# 11_FPGA_power.net
KiCad netlist of a schematic drawn in Altium Designer
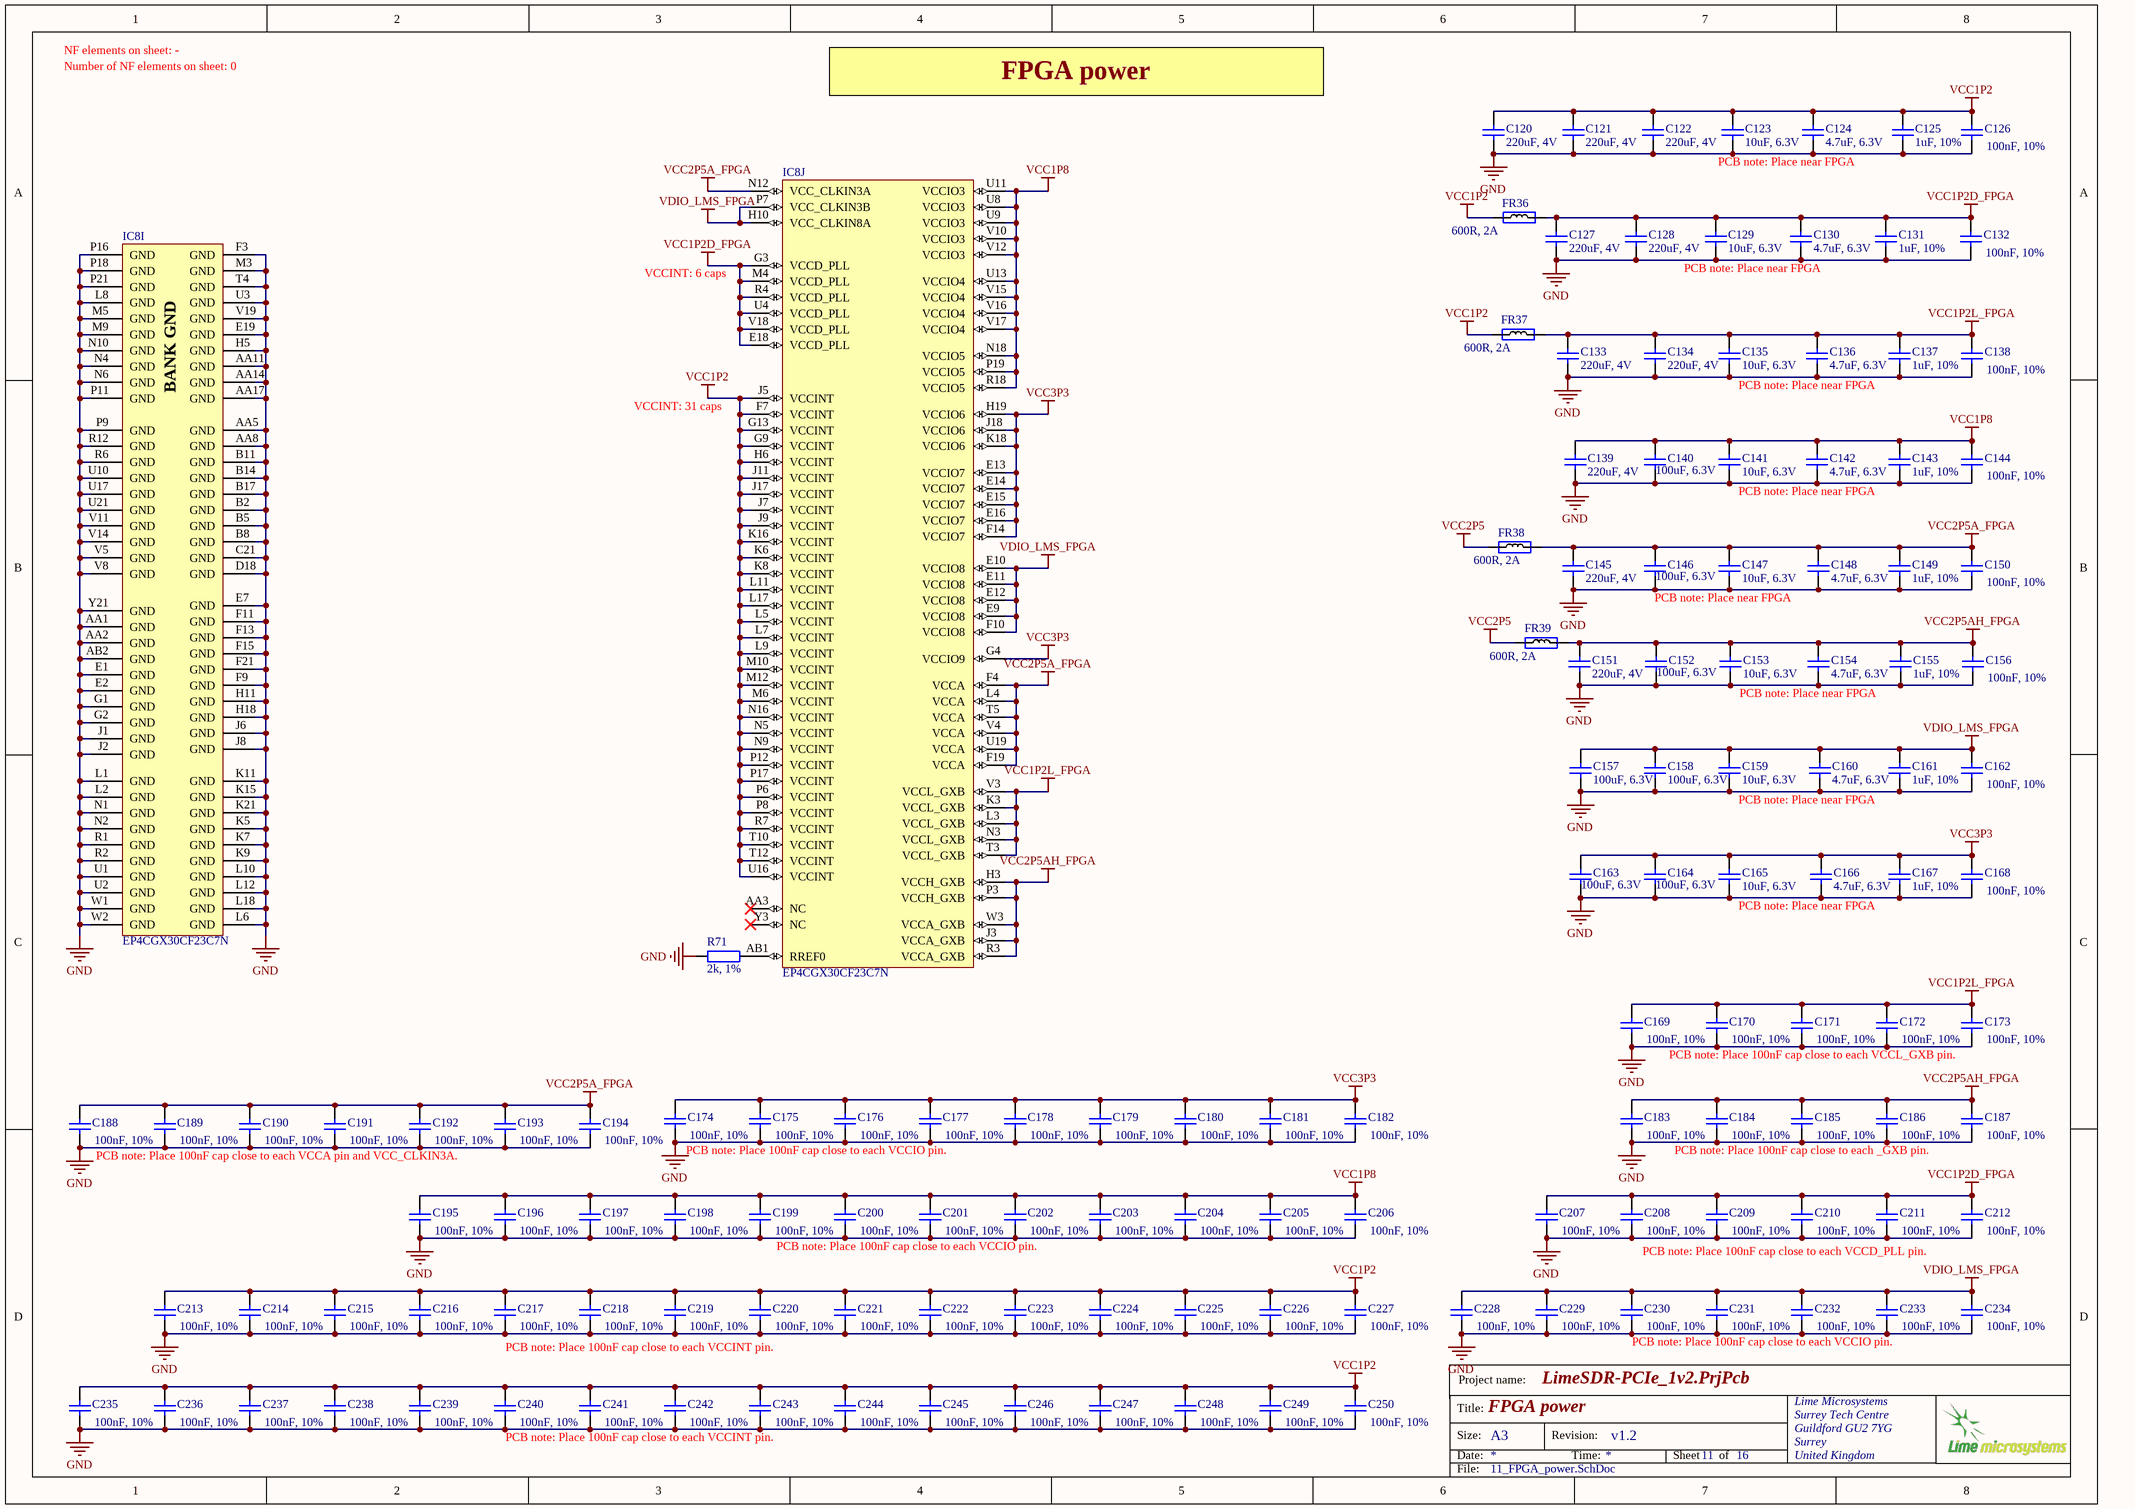
[diagram p0: 11_FPGA_power.SchDoc]

(export (version "E")
  (design (tool "Eeschema 10.0.6"))
  (components
    (comp (ref "C120")
      (value "220uF, 4V")
      (footprint "CAP1206")
      (fields
        (field (name "MANUFACTURER PART NUMBER") "GRM31CR60G227ME11L")
        (field (name "MANUFACTURER") "Murata Electronics North America")
        (field (name "TOLERANCE") "±20%")
      )
      (libsource (lib "LimeFPGAboard_schLib") (part "Cap_1206"))
    )
    (comp (ref "C121")
      (value "220uF, 4V")
      (footprint "CAP1206")
      (fields
        (field (name "MANUFACTURER PART NUMBER") "GRM31CR60G227ME11L")
        (field (name "MANUFACTURER") "Murata Electronics North America")
        (field (name "TOLERANCE") "±20%")
      )
      (libsource (lib "LimeFPGAboard_schLib") (part "Cap_1206"))
    )
    (comp (ref "C122")
      (value "220uF, 4V")
      (footprint "CAP1206")
      (fields
        (field (name "MANUFACTURER PART NUMBER") "GRM31CR60G227ME11L")
        (field (name "MANUFACTURER") "Murata Electronics North America")
        (field (name "TOLERANCE") "±20%")
      )
      (libsource (lib "LimeFPGAboard_schLib") (part "Cap_1206"))
    )
    (comp (ref "C123")
      (value "10uF, 6.3V")
      (footprint "CAP0603")
      (fields (field (name "TOLERANCE") "±20%") (field (name "MANUFACTURER") "Yageo"))
      (libsource (lib "LimeFPGAboard_schLib") (part "Cap_0603"))
    )
    (comp (ref "C124")
      (value "4.7uF, 6.3V")
      (footprint "CAP0402")
      (fields
        (field (name "MANUFACTURER") "Murata Electronics North America")
        (field (name "TOLERANCE") "±20%")
      )
      (libsource (lib "LimeMicroAltiumLib_schLib") (part "Cap_0402"))
    )
    (comp (ref "C125")
      (value "1uF, 10%")
      (footprint "CAP0402")
      (fields (field (name "MANUFACTURER") "TDK"))
      (libsource (lib "LimeMicroAltiumLib_schLib") (part "Cap_0402"))
    )
    (comp (ref "C126")
      (value "100nF, 10%")
      (footprint "CAP0402")
      (fields
        (field (name "TOLERANCE") "10 %")
        (field (name "MANUFACTURER") "Murata Electronics")
        (field (name "MANUFACTURER PART NUMBER") "GRM155R71C104KA88D")
      )
      (libsource (lib "LimeFPGAboard_schLib") (part "Cap_0603"))
    )
    (comp (ref "C127")
      (value "220uF, 4V")
      (footprint "CAP1206")
      (fields
        (field (name "MANUFACTURER PART NUMBER") "GRM31CR60G227ME11L")
        (field (name "MANUFACTURER") "Murata Electronics North America")
        (field (name "TOLERANCE") "±20%")
      )
      (libsource (lib "LimeFPGAboard_schLib") (part "Cap_1206"))
    )
    (comp (ref "C128")
      (value "220uF, 4V")
      (footprint "CAP1206")
      (fields
        (field (name "MANUFACTURER PART NUMBER") "GRM31CR60G227ME11L")
        (field (name "MANUFACTURER") "Murata Electronics North America")
        (field (name "TOLERANCE") "±20%")
      )
      (libsource (lib "LimeFPGAboard_schLib") (part "Cap_1206"))
    )
    (comp (ref "C129")
      (value "10uF, 6.3V")
      (footprint "CAP0603")
      (fields (field (name "TOLERANCE") "±20%") (field (name "MANUFACTURER") "Yageo"))
      (libsource (lib "LimeFPGAboard_schLib") (part "Cap_0603"))
    )
    (comp (ref "C130")
      (value "4.7uF, 6.3V")
      (footprint "CAP0402")
      (fields
        (field (name "MANUFACTURER") "Murata Electronics North America")
        (field (name "TOLERANCE") "±20%")
      )
      (libsource (lib "LimeMicroAltiumLib_schLib") (part "Cap_0402"))
    )
    (comp (ref "C131")
      (value "1uF, 10%")
      (footprint "CAP0402")
      (fields (field (name "MANUFACTURER") "TDK"))
      (libsource (lib "LimeMicroAltiumLib_schLib") (part "Cap_0402"))
    )
    (comp (ref "C132")
      (value "100nF, 10%")
      (footprint "CAP0402")
      (fields
        (field (name "TOLERANCE") "10 %")
        (field (name "MANUFACTURER") "Murata Electronics")
        (field (name "MANUFACTURER PART NUMBER") "GRM155R71C104KA88D")
      )
      (libsource (lib "LimeFPGAboard_schLib") (part "Cap_0603"))
    )
    (comp (ref "C133")
      (value "220uF, 4V")
      (footprint "CAP1206")
      (fields
        (field (name "MANUFACTURER PART NUMBER") "GRM31CR60G227ME11L")
        (field (name "MANUFACTURER") "Murata Electronics North America")
        (field (name "TOLERANCE") "±20%")
      )
      (libsource (lib "LimeFPGAboard_schLib") (part "Cap_1206"))
    )
    (comp (ref "C134")
      (value "220uF, 4V")
      (footprint "CAP1206")
      (fields
        (field (name "MANUFACTURER PART NUMBER") "GRM31CR60G227ME11L")
        (field (name "MANUFACTURER") "Murata Electronics North America")
        (field (name "TOLERANCE") "±20%")
      )
      (libsource (lib "LimeFPGAboard_schLib") (part "Cap_1206"))
    )
    (comp (ref "C135")
      (value "10uF, 6.3V")
      (footprint "CAP0603")
      (fields (field (name "TOLERANCE") "±20%") (field (name "MANUFACTURER") "Yageo"))
      (libsource (lib "LimeFPGAboard_schLib") (part "Cap_0603"))
    )
    (comp (ref "C136")
      (value "4.7uF, 6.3V")
      (footprint "CAP0402")
      (fields
        (field (name "MANUFACTURER") "Murata Electronics North America")
        (field (name "TOLERANCE") "±20%")
      )
      (libsource (lib "LimeMicroAltiumLib_schLib") (part "Cap_0402"))
    )
    (comp (ref "C137")
      (value "1uF, 10%")
      (footprint "CAP0402")
      (fields (field (name "MANUFACTURER") "TDK"))
      (libsource (lib "LimeMicroAltiumLib_schLib") (part "Cap_0402"))
    )
    (comp (ref "C138")
      (value "100nF, 10%")
      (footprint "CAP0402")
      (fields
        (field (name "TOLERANCE") "10 %")
        (field (name "MANUFACTURER") "Murata Electronics")
        (field (name "MANUFACTURER PART NUMBER") "GRM155R71C104KA88D")
      )
      (libsource (lib "LimeFPGAboard_schLib") (part "Cap_0603"))
    )
    (comp (ref "C139")
      (value "220uF, 4V")
      (footprint "CAP1206")
      (fields
        (field (name "MANUFACTURER PART NUMBER") "GRM31CR60G227ME11L")
        (field (name "MANUFACTURER") "Murata Electronics North America")
        (field (name "TOLERANCE") "±20%")
      )
      (libsource (lib "LimeFPGAboard_schLib") (part "Cap_1206"))
    )
    (comp (ref "C140")
      (value "100uF, 6.3V")
      (footprint "CAP1206")
      (fields (field (name "MANUFACTURER") "MURATA"))
      (libsource (lib "LimeFPGAboard_schLib") (part "Cap_1206"))
    )
    (comp (ref "C141")
      (value "10uF, 6.3V")
      (footprint "CAP0603")
      (fields (field (name "TOLERANCE") "±20%") (field (name "MANUFACTURER") "Yageo"))
      (libsource (lib "LimeFPGAboard_schLib") (part "Cap_0603"))
    )
    (comp (ref "C142")
      (value "4.7uF, 6.3V")
      (footprint "CAP0402")
      (fields
        (field (name "MANUFACTURER") "Murata Electronics North America")
        (field (name "TOLERANCE") "±20%")
      )
      (libsource (lib "LimeMicroAltiumLib_schLib") (part "Cap_0402"))
    )
    (comp (ref "C143")
      (value "1uF, 10%")
      (footprint "CAP0402")
      (fields (field (name "MANUFACTURER") "TDK"))
      (libsource (lib "LimeMicroAltiumLib_schLib") (part "Cap_0402"))
    )
    (comp (ref "C144")
      (value "100nF, 10%")
      (footprint "CAP0402")
      (fields
        (field (name "TOLERANCE") "10 %")
        (field (name "MANUFACTURER") "Murata Electronics")
        (field (name "MANUFACTURER PART NUMBER") "GRM155R71C104KA88D")
      )
      (libsource (lib "LimeFPGAboard_schLib") (part "Cap_0603"))
    )
    (comp (ref "C145")
      (value "220uF, 4V")
      (footprint "CAP1206")
      (fields
        (field (name "MANUFACTURER PART NUMBER") "GRM31CR60G227ME11L")
        (field (name "MANUFACTURER") "Murata Electronics North America")
        (field (name "TOLERANCE") "±20%")
      )
      (libsource (lib "LimeFPGAboard_schLib") (part "Cap_1206"))
    )
    (comp (ref "C146")
      (value "100uF, 6.3V")
      (footprint "CAP1206")
      (fields (field (name "MANUFACTURER") "MURATA"))
      (libsource (lib "LimeFPGAboard_schLib") (part "Cap_1206"))
    )
    (comp (ref "C147")
      (value "10uF, 6.3V")
      (footprint "CAP0603")
      (fields (field (name "TOLERANCE") "±20%") (field (name "MANUFACTURER") "Yageo"))
      (libsource (lib "LimeFPGAboard_schLib") (part "Cap_0603"))
    )
    (comp (ref "C148")
      (value "4.7uF, 6.3V")
      (footprint "CAP0402")
      (fields
        (field (name "MANUFACTURER") "Murata Electronics North America")
        (field (name "TOLERANCE") "±20%")
      )
      (libsource (lib "LimeMicroAltiumLib_schLib") (part "Cap_0402"))
    )
    (comp (ref "C149")
      (value "1uF, 10%")
      (footprint "CAP0402")
      (fields (field (name "MANUFACTURER") "TDK"))
      (libsource (lib "LimeMicroAltiumLib_schLib") (part "Cap_0402"))
    )
    (comp (ref "C150")
      (value "100nF, 10%")
      (footprint "CAP0402")
      (fields
        (field (name "TOLERANCE") "10 %")
        (field (name "MANUFACTURER") "Murata Electronics")
        (field (name "MANUFACTURER PART NUMBER") "GRM155R71C104KA88D")
      )
      (libsource (lib "LimeFPGAboard_schLib") (part "Cap_0603"))
    )
    (comp (ref "C151")
      (value "220uF, 4V")
      (footprint "CAP1206")
      (fields
        (field (name "MANUFACTURER PART NUMBER") "GRM31CR60G227ME11L")
        (field (name "MANUFACTURER") "Murata Electronics North America")
        (field (name "TOLERANCE") "±20%")
      )
      (libsource (lib "LimeFPGAboard_schLib") (part "Cap_1206"))
    )
    (comp (ref "C152")
      (value "100uF, 6.3V")
      (footprint "CAP1206")
      (fields (field (name "MANUFACTURER") "MURATA"))
      (libsource (lib "LimeFPGAboard_schLib") (part "Cap_1206"))
    )
    (comp (ref "C153")
      (value "10uF, 6.3V")
      (footprint "CAP0603")
      (fields (field (name "TOLERANCE") "±20%") (field (name "MANUFACTURER") "Yageo"))
      (libsource (lib "LimeFPGAboard_schLib") (part "Cap_0603"))
    )
    (comp (ref "C154")
      (value "4.7uF, 6.3V")
      (footprint "CAP0402")
      (fields
        (field (name "MANUFACTURER") "Murata Electronics North America")
        (field (name "TOLERANCE") "±20%")
      )
      (libsource (lib "LimeMicroAltiumLib_schLib") (part "Cap_0402"))
    )
    (comp (ref "C155")
      (value "1uF, 10%")
      (footprint "CAP0402")
      (fields (field (name "MANUFACTURER") "TDK"))
      (libsource (lib "LimeMicroAltiumLib_schLib") (part "Cap_0402"))
    )
    (comp (ref "C156")
      (value "100nF, 10%")
      (footprint "CAP0402")
      (fields
        (field (name "TOLERANCE") "10 %")
        (field (name "MANUFACTURER") "Murata Electronics")
        (field (name "MANUFACTURER PART NUMBER") "GRM155R71C104KA88D")
      )
      (libsource (lib "LimeFPGAboard_schLib") (part "Cap_0603"))
    )
    (comp (ref "C157")
      (value "100uF, 6.3V")
      (footprint "CAP1206")
      (fields (field (name "MANUFACTURER") "MURATA"))
      (libsource (lib "LimeFPGAboard_schLib") (part "Cap_1206"))
    )
    (comp (ref "C158")
      (value "100uF, 6.3V")
      (footprint "CAP1206")
      (fields (field (name "MANUFACTURER") "MURATA"))
      (libsource (lib "LimeFPGAboard_schLib") (part "Cap_1206"))
    )
    (comp (ref "C159")
      (value "10uF, 6.3V")
      (footprint "CAP0603")
      (fields (field (name "TOLERANCE") "±20%") (field (name "MANUFACTURER") "Yageo"))
      (libsource (lib "LimeFPGAboard_schLib") (part "Cap_0603"))
    )
    (comp (ref "C160")
      (value "4.7uF, 6.3V")
      (footprint "CAP0402")
      (fields
        (field (name "MANUFACTURER") "Murata Electronics North America")
        (field (name "TOLERANCE") "±20%")
      )
      (libsource (lib "LimeMicroAltiumLib_schLib") (part "Cap_0402"))
    )
    (comp (ref "C161")
      (value "1uF, 10%")
      (footprint "CAP0402")
      (fields (field (name "MANUFACTURER") "TDK"))
      (libsource (lib "LimeMicroAltiumLib_schLib") (part "Cap_0402"))
    )
    (comp (ref "C162")
      (value "100nF, 10%")
      (footprint "CAP0402")
      (fields
        (field (name "TOLERANCE") "10 %")
        (field (name "MANUFACTURER") "Murata Electronics")
        (field (name "MANUFACTURER PART NUMBER") "GRM155R71C104KA88D")
      )
      (libsource (lib "LimeFPGAboard_schLib") (part "Cap_0603"))
    )
    (comp (ref "C163")
      (value "100uF, 6.3V")
      (footprint "CAP1206")
      (fields (field (name "MANUFACTURER") "MURATA"))
      (libsource (lib "LimeFPGAboard_schLib") (part "Cap_1206"))
    )
    (comp (ref "C164")
      (value "100uF, 6.3V")
      (footprint "CAP1206")
      (fields (field (name "MANUFACTURER") "MURATA"))
      (libsource (lib "LimeFPGAboard_schLib") (part "Cap_1206"))
    )
    (comp (ref "C165")
      (value "10uF, 6.3V")
      (footprint "CAP0603")
      (fields (field (name "TOLERANCE") "±20%") (field (name "MANUFACTURER") "Yageo"))
      (libsource (lib "LimeFPGAboard_schLib") (part "Cap_0603"))
    )
    (comp (ref "C166")
      (value "4.7uF, 6.3V")
      (footprint "CAP0402")
      (fields
        (field (name "MANUFACTURER") "Murata Electronics North America")
        (field (name "TOLERANCE") "±20%")
      )
      (libsource (lib "LimeMicroAltiumLib_schLib") (part "Cap_0402"))
    )
    (comp (ref "C167")
      (value "1uF, 10%")
      (footprint "CAP0402")
      (fields (field (name "MANUFACTURER") "TDK"))
      (libsource (lib "LimeMicroAltiumLib_schLib") (part "Cap_0402"))
    )
    (comp (ref "C168")
      (value "100nF, 10%")
      (footprint "CAP0402")
      (fields
        (field (name "TOLERANCE") "10 %")
        (field (name "MANUFACTURER") "Murata Electronics")
        (field (name "MANUFACTURER PART NUMBER") "GRM155R71C104KA88D")
      )
      (libsource (lib "LimeFPGAboard_schLib") (part "Cap_0603"))
    )
    (comp (ref "C169")
      (value "100nF, 10%")
      (footprint "CAP0402")
      (fields
        (field (name "TOLERANCE") "10 %")
        (field (name "MANUFACTURER") "Murata Electronics")
        (field (name "MANUFACTURER PART NUMBER") "GRM155R71C104KA88D")
      )
      (libsource (lib "LimeFPGAboard_schLib") (part "Cap_0603"))
    )
    (comp (ref "C170")
      (value "100nF, 10%")
      (footprint "CAP0402")
      (fields
        (field (name "TOLERANCE") "10 %")
        (field (name "MANUFACTURER") "Murata Electronics")
        (field (name "MANUFACTURER PART NUMBER") "GRM155R71C104KA88D")
      )
      (libsource (lib "LimeFPGAboard_schLib") (part "Cap_0603"))
    )
    (comp (ref "C171")
      (value "100nF, 10%")
      (footprint "CAP0402")
      (fields
        (field (name "TOLERANCE") "10 %")
        (field (name "MANUFACTURER") "Murata Electronics")
        (field (name "MANUFACTURER PART NUMBER") "GRM155R71C104KA88D")
      )
      (libsource (lib "LimeFPGAboard_schLib") (part "Cap_0603"))
    )
    (comp (ref "C172")
      (value "100nF, 10%")
      (footprint "CAP0402")
      (fields
        (field (name "TOLERANCE") "10 %")
        (field (name "MANUFACTURER") "Murata Electronics")
        (field (name "MANUFACTURER PART NUMBER") "GRM155R71C104KA88D")
      )
      (libsource (lib "LimeFPGAboard_schLib") (part "Cap_0603"))
    )
    (comp (ref "C173")
      (value "100nF, 10%")
      (footprint "CAP0402")
      (fields
        (field (name "TOLERANCE") "10 %")
        (field (name "MANUFACTURER") "Murata Electronics")
        (field (name "MANUFACTURER PART NUMBER") "GRM155R71C104KA88D")
      )
      (libsource (lib "LimeFPGAboard_schLib") (part "Cap_0603"))
    )
    (comp (ref "C174")
      (value "100nF, 10%")
      (footprint "CAP0402")
      (fields
        (field (name "TOLERANCE") "10 %")
        (field (name "MANUFACTURER") "Murata Electronics")
        (field (name "MANUFACTURER PART NUMBER") "GRM155R71C104KA88D")
      )
      (libsource (lib "LimeFPGAboard_schLib") (part "Cap_0603"))
    )
    (comp (ref "C175")
      (value "100nF, 10%")
      (footprint "CAP0402")
      (fields
        (field (name "TOLERANCE") "10 %")
        (field (name "MANUFACTURER") "Murata Electronics")
        (field (name "MANUFACTURER PART NUMBER") "GRM155R71C104KA88D")
      )
      (libsource (lib "LimeFPGAboard_schLib") (part "Cap_0603"))
    )
    (comp (ref "C176")
      (value "100nF, 10%")
      (footprint "CAP0402")
      (fields
        (field (name "TOLERANCE") "10 %")
        (field (name "MANUFACTURER") "Murata Electronics")
        (field (name "MANUFACTURER PART NUMBER") "GRM155R71C104KA88D")
      )
      (libsource (lib "LimeFPGAboard_schLib") (part "Cap_0603"))
    )
    (comp (ref "C177")
      (value "100nF, 10%")
      (footprint "CAP0402")
      (fields
        (field (name "TOLERANCE") "10 %")
        (field (name "MANUFACTURER") "Murata Electronics")
        (field (name "MANUFACTURER PART NUMBER") "GRM155R71C104KA88D")
      )
      (libsource (lib "LimeFPGAboard_schLib") (part "Cap_0603"))
    )
    (comp (ref "C178")
      (value "100nF, 10%")
      (footprint "CAP0402")
      (fields
        (field (name "TOLERANCE") "10 %")
        (field (name "MANUFACTURER") "Murata Electronics")
        (field (name "MANUFACTURER PART NUMBER") "GRM155R71C104KA88D")
      )
      (libsource (lib "LimeFPGAboard_schLib") (part "Cap_0603"))
    )
    (comp (ref "C179")
      (value "100nF, 10%")
      (footprint "CAP0402")
      (fields
        (field (name "TOLERANCE") "10 %")
        (field (name "MANUFACTURER") "Murata Electronics")
        (field (name "MANUFACTURER PART NUMBER") "GRM155R71C104KA88D")
      )
      (libsource (lib "LimeFPGAboard_schLib") (part "Cap_0603"))
    )
    (comp (ref "C180")
      (value "100nF, 10%")
      (footprint "CAP0402")
      (fields
        (field (name "TOLERANCE") "10 %")
        (field (name "MANUFACTURER") "Murata Electronics")
        (field (name "MANUFACTURER PART NUMBER") "GRM155R71C104KA88D")
      )
      (libsource (lib "LimeFPGAboard_schLib") (part "Cap_0603"))
    )
    (comp (ref "C181")
      (value "100nF, 10%")
      (footprint "CAP0402")
      (fields
        (field (name "TOLERANCE") "10 %")
        (field (name "MANUFACTURER") "Murata Electronics")
        (field (name "MANUFACTURER PART NUMBER") "GRM155R71C104KA88D")
      )
      (libsource (lib "LimeFPGAboard_schLib") (part "Cap_0603"))
    )
    (comp (ref "C182")
      (value "100nF, 10%")
      (footprint "CAP0402")
      (fields
        (field (name "TOLERANCE") "10 %")
        (field (name "MANUFACTURER") "Murata Electronics")
        (field (name "MANUFACTURER PART NUMBER") "GRM155R71C104KA88D")
      )
      (libsource (lib "LimeFPGAboard_schLib") (part "Cap_0603"))
    )
    (comp (ref "C183")
      (value "100nF, 10%")
      (footprint "CAP0402")
      (fields
        (field (name "TOLERANCE") "10 %")
        (field (name "MANUFACTURER") "Murata Electronics")
        (field (name "MANUFACTURER PART NUMBER") "GRM155R71C104KA88D")
      )
      (libsource (lib "LimeFPGAboard_schLib") (part "Cap_0603"))
    )
    (comp (ref "C184")
      (value "100nF, 10%")
      (footprint "CAP0402")
      (fields
        (field (name "TOLERANCE") "10 %")
        (field (name "MANUFACTURER") "Murata Electronics")
        (field (name "MANUFACTURER PART NUMBER") "GRM155R71C104KA88D")
      )
      (libsource (lib "LimeFPGAboard_schLib") (part "Cap_0603"))
    )
    (comp (ref "C185")
      (value "100nF, 10%")
      (footprint "CAP0402")
      (fields
        (field (name "TOLERANCE") "10 %")
        (field (name "MANUFACTURER") "Murata Electronics")
        (field (name "MANUFACTURER PART NUMBER") "GRM155R71C104KA88D")
      )
      (libsource (lib "LimeFPGAboard_schLib") (part "Cap_0603"))
    )
    (comp (ref "C186")
      (value "100nF, 10%")
      (footprint "CAP0402")
      (fields
        (field (name "TOLERANCE") "10 %")
        (field (name "MANUFACTURER") "Murata Electronics")
        (field (name "MANUFACTURER PART NUMBER") "GRM155R71C104KA88D")
      )
      (libsource (lib "LimeFPGAboard_schLib") (part "Cap_0603"))
    )
    (comp (ref "C187")
      (value "100nF, 10%")
      (footprint "CAP0402")
      (fields
        (field (name "TOLERANCE") "10 %")
        (field (name "MANUFACTURER") "Murata Electronics")
        (field (name "MANUFACTURER PART NUMBER") "GRM155R71C104KA88D")
      )
      (libsource (lib "LimeFPGAboard_schLib") (part "Cap_0603"))
    )
    (comp (ref "C188")
      (value "100nF, 10%")
      (footprint "CAP0402")
      (fields
        (field (name "TOLERANCE") "10 %")
        (field (name "MANUFACTURER") "Murata Electronics")
        (field (name "MANUFACTURER PART NUMBER") "GRM155R71C104KA88D")
      )
      (libsource (lib "LimeFPGAboard_schLib") (part "Cap_0603"))
    )
    (comp (ref "C189")
      (value "100nF, 10%")
      (footprint "CAP0402")
      (fields
        (field (name "TOLERANCE") "10 %")
        (field (name "MANUFACTURER") "Murata Electronics")
        (field (name "MANUFACTURER PART NUMBER") "GRM155R71C104KA88D")
      )
      (libsource (lib "LimeFPGAboard_schLib") (part "Cap_0603"))
    )
    (comp (ref "C190")
      (value "100nF, 10%")
      (footprint "CAP0402")
      (fields
        (field (name "TOLERANCE") "10 %")
        (field (name "MANUFACTURER") "Murata Electronics")
        (field (name "MANUFACTURER PART NUMBER") "GRM155R71C104KA88D")
      )
      (libsource (lib "LimeFPGAboard_schLib") (part "Cap_0603"))
    )
    (comp (ref "C191")
      (value "100nF, 10%")
      (footprint "CAP0402")
      (fields
        (field (name "TOLERANCE") "10 %")
        (field (name "MANUFACTURER") "Murata Electronics")
        (field (name "MANUFACTURER PART NUMBER") "GRM155R71C104KA88D")
      )
      (libsource (lib "LimeFPGAboard_schLib") (part "Cap_0603"))
    )
    (comp (ref "C192")
      (value "100nF, 10%")
      (footprint "CAP0402")
      (fields
        (field (name "TOLERANCE") "10 %")
        (field (name "MANUFACTURER") "Murata Electronics")
        (field (name "MANUFACTURER PART NUMBER") "GRM155R71C104KA88D")
      )
      (libsource (lib "LimeFPGAboard_schLib") (part "Cap_0603"))
    )
    (comp (ref "C193")
      (value "100nF, 10%")
      (footprint "CAP0402")
      (fields
        (field (name "TOLERANCE") "10 %")
        (field (name "MANUFACTURER") "Murata Electronics")
        (field (name "MANUFACTURER PART NUMBER") "GRM155R71C104KA88D")
      )
      (libsource (lib "LimeFPGAboard_schLib") (part "Cap_0603"))
    )
    (comp (ref "C194")
      (value "100nF, 10%")
      (footprint "CAP0402")
      (fields
        (field (name "TOLERANCE") "10 %")
        (field (name "MANUFACTURER") "Murata Electronics")
        (field (name "MANUFACTURER PART NUMBER") "GRM155R71C104KA88D")
      )
      (libsource (lib "LimeFPGAboard_schLib") (part "Cap_0603"))
    )
    (comp (ref "C195")
      (value "100nF, 10%")
      (footprint "CAP0402")
      (fields
        (field (name "TOLERANCE") "10 %")
        (field (name "MANUFACTURER") "Murata Electronics")
        (field (name "MANUFACTURER PART NUMBER") "GRM155R71C104KA88D")
      )
      (libsource (lib "LimeFPGAboard_schLib") (part "Cap_0603"))
    )
    (comp (ref "C196")
      (value "100nF, 10%")
      (footprint "CAP0402")
      (fields
        (field (name "TOLERANCE") "10 %")
        (field (name "MANUFACTURER") "Murata Electronics")
        (field (name "MANUFACTURER PART NUMBER") "GRM155R71C104KA88D")
      )
      (libsource (lib "LimeFPGAboard_schLib") (part "Cap_0603"))
    )
    (comp (ref "C197")
      (value "100nF, 10%")
      (footprint "CAP0402")
      (fields
        (field (name "TOLERANCE") "10 %")
        (field (name "MANUFACTURER") "Murata Electronics")
        (field (name "MANUFACTURER PART NUMBER") "GRM155R71C104KA88D")
      )
      (libsource (lib "LimeFPGAboard_schLib") (part "Cap_0603"))
    )
    (comp (ref "C198")
      (value "100nF, 10%")
      (footprint "CAP0402")
      (fields
        (field (name "TOLERANCE") "10 %")
        (field (name "MANUFACTURER") "Murata Electronics")
        (field (name "MANUFACTURER PART NUMBER") "GRM155R71C104KA88D")
      )
      (libsource (lib "LimeFPGAboard_schLib") (part "Cap_0603"))
    )
    (comp (ref "C199")
      (value "100nF, 10%")
      (footprint "CAP0402")
      (fields
        (field (name "TOLERANCE") "10 %")
        (field (name "MANUFACTURER") "Murata Electronics")
        (field (name "MANUFACTURER PART NUMBER") "GRM155R71C104KA88D")
      )
      (libsource (lib "LimeFPGAboard_schLib") (part "Cap_0603"))
    )
    (comp (ref "C200")
      (value "100nF, 10%")
      (footprint "CAP0402")
      (fields
        (field (name "TOLERANCE") "10 %")
        (field (name "MANUFACTURER") "Murata Electronics")
        (field (name "MANUFACTURER PART NUMBER") "GRM155R71C104KA88D")
      )
      (libsource (lib "LimeFPGAboard_schLib") (part "Cap_0603"))
    )
    (comp (ref "C201")
      (value "100nF, 10%")
      (footprint "CAP0402")
      (fields
        (field (name "TOLERANCE") "10 %")
        (field (name "MANUFACTURER") "Murata Electronics")
        (field (name "MANUFACTURER PART NUMBER") "GRM155R71C104KA88D")
      )
      (libsource (lib "LimeFPGAboard_schLib") (part "Cap_0603"))
    )
    (comp (ref "C202")
      (value "100nF, 10%")
      (footprint "CAP0402")
      (fields
        (field (name "TOLERANCE") "10 %")
        (field (name "MANUFACTURER") "Murata Electronics")
        (field (name "MANUFACTURER PART NUMBER") "GRM155R71C104KA88D")
      )
      (libsource (lib "LimeFPGAboard_schLib") (part "Cap_0603"))
    )
    (comp (ref "C203")
      (value "100nF, 10%")
      (footprint "CAP0402")
      (fields
        (field (name "TOLERANCE") "10 %")
        (field (name "MANUFACTURER") "Murata Electronics")
        (field (name "MANUFACTURER PART NUMBER") "GRM155R71C104KA88D")
      )
      (libsource (lib "LimeFPGAboard_schLib") (part "Cap_0603"))
    )
    (comp (ref "C204")
      (value "100nF, 10%")
      (footprint "CAP0402")
      (fields
        (field (name "TOLERANCE") "10 %")
        (field (name "MANUFACTURER") "Murata Electronics")
        (field (name "MANUFACTURER PART NUMBER") "GRM155R71C104KA88D")
      )
      (libsource (lib "LimeFPGAboard_schLib") (part "Cap_0603"))
    )
    (comp (ref "C205")
      (value "100nF, 10%")
      (footprint "CAP0402")
      (fields
        (field (name "TOLERANCE") "10 %")
        (field (name "MANUFACTURER") "Murata Electronics")
        (field (name "MANUFACTURER PART NUMBER") "GRM155R71C104KA88D")
      )
      (libsource (lib "LimeFPGAboard_schLib") (part "Cap_0603"))
    )
    (comp (ref "C206")
      (value "100nF, 10%")
      (footprint "CAP0402")
      (fields
        (field (name "TOLERANCE") "10 %")
        (field (name "MANUFACTURER") "Murata Electronics")
        (field (name "MANUFACTURER PART NUMBER") "GRM155R71C104KA88D")
      )
      (libsource (lib "LimeFPGAboard_schLib") (part "Cap_0603"))
    )
    (comp (ref "C207")
      (value "100nF, 10%")
      (footprint "CAP0402")
      (fields
        (field (name "TOLERANCE") "10 %")
        (field (name "MANUFACTURER") "Murata Electronics")
        (field (name "MANUFACTURER PART NUMBER") "GRM155R71C104KA88D")
      )
      (libsource (lib "LimeFPGAboard_schLib") (part "Cap_0603"))
    )
    (comp (ref "C208")
      (value "100nF, 10%")
      (footprint "CAP0402")
      (fields
        (field (name "TOLERANCE") "10 %")
        (field (name "MANUFACTURER") "Murata Electronics")
        (field (name "MANUFACTURER PART NUMBER") "GRM155R71C104KA88D")
      )
      (libsource (lib "LimeFPGAboard_schLib") (part "Cap_0603"))
    )
    (comp (ref "C209")
      (value "100nF, 10%")
      (footprint "CAP0402")
      (fields
        (field (name "TOLERANCE") "10 %")
        (field (name "MANUFACTURER") "Murata Electronics")
        (field (name "MANUFACTURER PART NUMBER") "GRM155R71C104KA88D")
      )
      (libsource (lib "LimeFPGAboard_schLib") (part "Cap_0603"))
    )
    (comp (ref "C210")
      (value "100nF, 10%")
      (footprint "CAP0402")
      (fields
        (field (name "TOLERANCE") "10 %")
        (field (name "MANUFACTURER") "Murata Electronics")
        (field (name "MANUFACTURER PART NUMBER") "GRM155R71C104KA88D")
      )
      (libsource (lib "LimeFPGAboard_schLib") (part "Cap_0603"))
    )
    (comp (ref "C211")
      (value "100nF, 10%")
      (footprint "CAP0402")
      (fields
        (field (name "TOLERANCE") "10 %")
        (field (name "MANUFACTURER") "Murata Electronics")
        (field (name "MANUFACTURER PART NUMBER") "GRM155R71C104KA88D")
      )
      (libsource (lib "LimeFPGAboard_schLib") (part "Cap_0603"))
    )
    (comp (ref "C212")
      (value "100nF, 10%")
      (footprint "CAP0402")
      (fields
        (field (name "TOLERANCE") "10 %")
        (field (name "MANUFACTURER") "Murata Electronics")
        (field (name "MANUFACTURER PART NUMBER") "GRM155R71C104KA88D")
      )
      (libsource (lib "LimeFPGAboard_schLib") (part "Cap_0603"))
    )
    (comp (ref "C213")
      (value "100nF, 10%")
      (footprint "CAP0402")
      (fields
        (field (name "TOLERANCE") "10 %")
        (field (name "MANUFACTURER") "Murata Electronics")
        (field (name "MANUFACTURER PART NUMBER") "GRM155R71C104KA88D")
      )
      (libsource (lib "LimeFPGAboard_schLib") (part "Cap_0603"))
    )
    (comp (ref "C214")
      (value "100nF, 10%")
      (footprint "CAP0402")
      (fields
        (field (name "TOLERANCE") "10 %")
        (field (name "MANUFACTURER") "Murata Electronics")
        (field (name "MANUFACTURER PART NUMBER") "GRM155R71C104KA88D")
      )
      (libsource (lib "LimeFPGAboard_schLib") (part "Cap_0603"))
    )
    (comp (ref "C215")
      (value "100nF, 10%")
      (footprint "CAP0402")
      (fields
        (field (name "TOLERANCE") "10 %")
        (field (name "MANUFACTURER") "Murata Electronics")
        (field (name "MANUFACTURER PART NUMBER") "GRM155R71C104KA88D")
      )
      (libsource (lib "LimeFPGAboard_schLib") (part "Cap_0603"))
    )
    (comp (ref "C216")
      (value "100nF, 10%")
      (footprint "CAP0402")
      (fields
        (field (name "TOLERANCE") "10 %")
        (field (name "MANUFACTURER") "Murata Electronics")
        (field (name "MANUFACTURER PART NUMBER") "GRM155R71C104KA88D")
      )
      (libsource (lib "LimeFPGAboard_schLib") (part "Cap_0603"))
    )
    (comp (ref "C217")
      (value "100nF, 10%")
      (footprint "CAP0402")
      (fields
        (field (name "TOLERANCE") "10 %")
        (field (name "MANUFACTURER") "Murata Electronics")
        (field (name "MANUFACTURER PART NUMBER") "GRM155R71C104KA88D")
      )
      (libsource (lib "LimeFPGAboard_schLib") (part "Cap_0603"))
    )
    (comp (ref "C218")
      (value "100nF, 10%")
      (footprint "CAP0402")
      (fields
        (field (name "TOLERANCE") "10 %")
        (field (name "MANUFACTURER") "Murata Electronics")
        (field (name "MANUFACTURER PART NUMBER") "GRM155R71C104KA88D")
      )
      (libsource (lib "LimeFPGAboard_schLib") (part "Cap_0603"))
    )
    (comp (ref "C219")
      (value "100nF, 10%")
      (footprint "CAP0402")
      (fields
        (field (name "TOLERANCE") "10 %")
        (field (name "MANUFACTURER") "Murata Electronics")
        (field (name "MANUFACTURER PART NUMBER") "GRM155R71C104KA88D")
      )
      (libsource (lib "LimeFPGAboard_schLib") (part "Cap_0603"))
    )
    (comp (ref "C220")
      (value "100nF, 10%")
      (footprint "CAP0402")
      (fields
        (field (name "TOLERANCE") "10 %")
        (field (name "MANUFACTURER") "Murata Electronics")
        (field (name "MANUFACTURER PART NUMBER") "GRM155R71C104KA88D")
      )
      (libsource (lib "LimeFPGAboard_schLib") (part "Cap_0603"))
    )
    (comp (ref "C221")
      (value "100nF, 10%")
      (footprint "CAP0402")
      (fields
        (field (name "TOLERANCE") "10 %")
        (field (name "MANUFACTURER") "Murata Electronics")
        (field (name "MANUFACTURER PART NUMBER") "GRM155R71C104KA88D")
      )
      (libsource (lib "LimeFPGAboard_schLib") (part "Cap_0603"))
    )
    (comp (ref "C222")
      (value "100nF, 10%")
      (footprint "CAP0402")
      (fields
        (field (name "TOLERANCE") "10 %")
        (field (name "MANUFACTURER") "Murata Electronics")
        (field (name "MANUFACTURER PART NUMBER") "GRM155R71C104KA88D")
      )
      (libsource (lib "LimeFPGAboard_schLib") (part "Cap_0603"))
    )
    (comp (ref "C223")
      (value "100nF, 10%")
      (footprint "CAP0402")
      (fields
        (field (name "TOLERANCE") "10 %")
        (field (name "MANUFACTURER") "Murata Electronics")
        (field (name "MANUFACTURER PART NUMBER") "GRM155R71C104KA88D")
      )
      (libsource (lib "LimeFPGAboard_schLib") (part "Cap_0603"))
    )
    (comp (ref "C224")
      (value "100nF, 10%")
      (footprint "CAP0402")
      (fields
        (field (name "TOLERANCE") "10 %")
        (field (name "MANUFACTURER") "Murata Electronics")
        (field (name "MANUFACTURER PART NUMBER") "GRM155R71C104KA88D")
      )
      (libsource (lib "LimeFPGAboard_schLib") (part "Cap_0603"))
    )
    (comp (ref "C225")
      (value "100nF, 10%")
      (footprint "CAP0402")
      (fields
        (field (name "TOLERANCE") "10 %")
        (field (name "MANUFACTURER") "Murata Electronics")
        (field (name "MANUFACTURER PART NUMBER") "GRM155R71C104KA88D")
      )
      (libsource (lib "LimeFPGAboard_schLib") (part "Cap_0603"))
    )
    (comp (ref "C226")
      (value "100nF, 10%")
      (footprint "CAP0402")
      (fields
        (field (name "TOLERANCE") "10 %")
        (field (name "MANUFACTURER") "Murata Electronics")
        (field (name "MANUFACTURER PART NUMBER") "GRM155R71C104KA88D")
      )
      (libsource (lib "LimeFPGAboard_schLib") (part "Cap_0603"))
    )
    (comp (ref "C227")
      (value "100nF, 10%")
      (footprint "CAP0402")
      (fields
        (field (name "TOLERANCE") "10 %")
        (field (name "MANUFACTURER") "Murata Electronics")
        (field (name "MANUFACTURER PART NUMBER") "GRM155R71C104KA88D")
      )
      (libsource (lib "LimeFPGAboard_schLib") (part "Cap_0603"))
    )
    (comp (ref "C228")
      (value "100nF, 10%")
      (footprint "CAP0402")
      (fields
        (field (name "TOLERANCE") "10 %")
        (field (name "MANUFACTURER") "Murata Electronics")
        (field (name "MANUFACTURER PART NUMBER") "GRM155R71C104KA88D")
      )
      (libsource (lib "LimeFPGAboard_schLib") (part "Cap_0603"))
    )
    (comp (ref "C229")
      (value "100nF, 10%")
      (footprint "CAP0402")
      (fields
        (field (name "TOLERANCE") "10 %")
        (field (name "MANUFACTURER") "Murata Electronics")
        (field (name "MANUFACTURER PART NUMBER") "GRM155R71C104KA88D")
      )
      (libsource (lib "LimeFPGAboard_schLib") (part "Cap_0603"))
    )
    (comp (ref "C230")
      (value "100nF, 10%")
      (footprint "CAP0402")
      (fields
        (field (name "TOLERANCE") "10 %")
        (field (name "MANUFACTURER") "Murata Electronics")
        (field (name "MANUFACTURER PART NUMBER") "GRM155R71C104KA88D")
      )
      (libsource (lib "LimeFPGAboard_schLib") (part "Cap_0603"))
    )
    (comp (ref "C231")
      (value "100nF, 10%")
      (footprint "CAP0402")
      (fields
        (field (name "TOLERANCE") "10 %")
        (field (name "MANUFACTURER") "Murata Electronics")
        (field (name "MANUFACTURER PART NUMBER") "GRM155R71C104KA88D")
      )
      (libsource (lib "LimeFPGAboard_schLib") (part "Cap_0603"))
    )
    (comp (ref "C232")
      (value "100nF, 10%")
      (footprint "CAP0402")
      (fields
        (field (name "TOLERANCE") "10 %")
        (field (name "MANUFACTURER") "Murata Electronics")
        (field (name "MANUFACTURER PART NUMBER") "GRM155R71C104KA88D")
      )
      (libsource (lib "LimeFPGAboard_schLib") (part "Cap_0603"))
    )
    (comp (ref "C233")
      (value "100nF, 10%")
      (footprint "CAP0402")
      (fields
        (field (name "TOLERANCE") "10 %")
        (field (name "MANUFACTURER") "Murata Electronics")
        (field (name "MANUFACTURER PART NUMBER") "GRM155R71C104KA88D")
      )
      (libsource (lib "LimeFPGAboard_schLib") (part "Cap_0603"))
    )
    (comp (ref "C234")
      (value "100nF, 10%")
      (footprint "CAP0402")
      (fields
        (field (name "TOLERANCE") "10 %")
        (field (name "MANUFACTURER") "Murata Electronics")
        (field (name "MANUFACTURER PART NUMBER") "GRM155R71C104KA88D")
      )
      (libsource (lib "LimeFPGAboard_schLib") (part "Cap_0603"))
    )
    (comp (ref "C235")
      (value "100nF, 10%")
      (footprint "CAP0402")
      (fields
        (field (name "TOLERANCE") "10 %")
        (field (name "MANUFACTURER") "Murata Electronics")
        (field (name "MANUFACTURER PART NUMBER") "GRM155R71C104KA88D")
      )
      (libsource (lib "LimeFPGAboard_schLib") (part "Cap_0603"))
    )
    (comp (ref "C236")
      (value "100nF, 10%")
      (footprint "CAP0402")
      (fields
        (field (name "TOLERANCE") "10 %")
        (field (name "MANUFACTURER") "Murata Electronics")
        (field (name "MANUFACTURER PART NUMBER") "GRM155R71C104KA88D")
      )
      (libsource (lib "LimeFPGAboard_schLib") (part "Cap_0603"))
    )
    (comp (ref "C237")
      (value "100nF, 10%")
      (footprint "CAP0402")
      (fields
        (field (name "TOLERANCE") "10 %")
        (field (name "MANUFACTURER") "Murata Electronics")
        (field (name "MANUFACTURER PART NUMBER") "GRM155R71C104KA88D")
      )
      (libsource (lib "LimeFPGAboard_schLib") (part "Cap_0603"))
    )
    (comp (ref "C238")
      (value "100nF, 10%")
      (footprint "CAP0402")
      (fields
        (field (name "TOLERANCE") "10 %")
        (field (name "MANUFACTURER") "Murata Electronics")
        (field (name "MANUFACTURER PART NUMBER") "GRM155R71C104KA88D")
      )
      (libsource (lib "LimeFPGAboard_schLib") (part "Cap_0603"))
    )
    (comp (ref "C239")
      (value "100nF, 10%")
      (footprint "CAP0402")
      (fields
        (field (name "TOLERANCE") "10 %")
        (field (name "MANUFACTURER") "Murata Electronics")
        (field (name "MANUFACTURER PART NUMBER") "GRM155R71C104KA88D")
      )
      (libsource (lib "LimeFPGAboard_schLib") (part "Cap_0603"))
    )
    (comp (ref "C240")
      (value "100nF, 10%")
      (footprint "CAP0402")
      (fields
        (field (name "TOLERANCE") "10 %")
        (field (name "MANUFACTURER") "Murata Electronics")
        (field (name "MANUFACTURER PART NUMBER") "GRM155R71C104KA88D")
      )
      (libsource (lib "LimeFPGAboard_schLib") (part "Cap_0603"))
    )
    (comp (ref "C241")
      (value "100nF, 10%")
      (footprint "CAP0402")
      (fields
        (field (name "TOLERANCE") "10 %")
        (field (name "MANUFACTURER") "Murata Electronics")
        (field (name "MANUFACTURER PART NUMBER") "GRM155R71C104KA88D")
      )
      (libsource (lib "LimeFPGAboard_schLib") (part "Cap_0603"))
    )
    (comp (ref "C242")
      (value "100nF, 10%")
      (footprint "CAP0402")
      (fields
        (field (name "TOLERANCE") "10 %")
        (field (name "MANUFACTURER") "Murata Electronics")
        (field (name "MANUFACTURER PART NUMBER") "GRM155R71C104KA88D")
      )
      (libsource (lib "LimeFPGAboard_schLib") (part "Cap_0603"))
    )
    (comp (ref "C243")
      (value "100nF, 10%")
      (footprint "CAP0402")
      (fields
        (field (name "TOLERANCE") "10 %")
        (field (name "MANUFACTURER") "Murata Electronics")
        (field (name "MANUFACTURER PART NUMBER") "GRM155R71C104KA88D")
      )
      (libsource (lib "LimeFPGAboard_schLib") (part "Cap_0603"))
    )
    (comp (ref "C244")
      (value "100nF, 10%")
      (footprint "CAP0402")
      (fields
        (field (name "TOLERANCE") "10 %")
        (field (name "MANUFACTURER") "Murata Electronics")
        (field (name "MANUFACTURER PART NUMBER") "GRM155R71C104KA88D")
      )
      (libsource (lib "LimeFPGAboard_schLib") (part "Cap_0603"))
    )
    (comp (ref "C245")
      (value "100nF, 10%")
      (footprint "CAP0402")
      (fields
        (field (name "TOLERANCE") "10 %")
        (field (name "MANUFACTURER") "Murata Electronics")
        (field (name "MANUFACTURER PART NUMBER") "GRM155R71C104KA88D")
      )
      (libsource (lib "LimeFPGAboard_schLib") (part "Cap_0603"))
    )
    (comp (ref "C246")
      (value "100nF, 10%")
      (footprint "CAP0402")
      (fields
        (field (name "TOLERANCE") "10 %")
        (field (name "MANUFACTURER") "Murata Electronics")
        (field (name "MANUFACTURER PART NUMBER") "GRM155R71C104KA88D")
      )
      (libsource (lib "LimeFPGAboard_schLib") (part "Cap_0603"))
    )
    (comp (ref "C247")
      (value "100nF, 10%")
      (footprint "CAP0402")
      (fields
        (field (name "TOLERANCE") "10 %")
        (field (name "MANUFACTURER") "Murata Electronics")
        (field (name "MANUFACTURER PART NUMBER") "GRM155R71C104KA88D")
      )
      (libsource (lib "LimeFPGAboard_schLib") (part "Cap_0603"))
    )
    (comp (ref "C248")
      (value "100nF, 10%")
      (footprint "CAP0402")
      (fields
        (field (name "TOLERANCE") "10 %")
        (field (name "MANUFACTURER") "Murata Electronics")
        (field (name "MANUFACTURER PART NUMBER") "GRM155R71C104KA88D")
      )
      (libsource (lib "LimeFPGAboard_schLib") (part "Cap_0603"))
    )
    (comp (ref "C249")
      (value "100nF, 10%")
      (footprint "CAP0402")
      (fields
        (field (name "TOLERANCE") "10 %")
        (field (name "MANUFACTURER") "Murata Electronics")
        (field (name "MANUFACTURER PART NUMBER") "GRM155R71C104KA88D")
      )
      (libsource (lib "LimeFPGAboard_schLib") (part "Cap_0603"))
    )
    (comp (ref "C250")
      (value "100nF, 10%")
      (footprint "CAP0402")
      (fields
        (field (name "TOLERANCE") "10 %")
        (field (name "MANUFACTURER") "Murata Electronics")
        (field (name "MANUFACTURER PART NUMBER") "GRM155R71C104KA88D")
      )
      (libsource (lib "LimeFPGAboard_schLib") (part "Cap_0603"))
    )
    (comp (ref "FR36")
      (value "600R, 2A")
      (footprint "RES0805")
      (fields (field (name "MANUFACTURER") "TDK Corporation"))
      (libsource (lib "LimeMicroAltiumLib_schLib") (part "Ferrite"))
    )
    (comp (ref "FR37")
      (value "600R, 2A")
      (footprint "RES0805")
      (fields (field (name "MANUFACTURER") "TDK Corporation"))
      (libsource (lib "LimeMicroAltiumLib_schLib") (part "Ferrite"))
    )
    (comp (ref "FR38")
      (value "600R, 2A")
      (footprint "RES0805")
      (fields (field (name "MANUFACTURER") "TDK Corporation"))
      (libsource (lib "LimeMicroAltiumLib_schLib") (part "Ferrite"))
    )
    (comp (ref "FR39")
      (value "600R, 2A")
      (footprint "RES0805")
      (fields (field (name "MANUFACTURER") "TDK Corporation"))
      (libsource (lib "LimeMicroAltiumLib_schLib") (part "Ferrite"))
    )
    (comp (ref "IC8")
      (value "EP4CGX30CF23C7N")
      (footprint "ALTR-FBGA484_A-200")
      (fields (field (name "MANUFACTURER") "Altera"))
      (libsource (lib "LimeMicroAltiumLib_schLib") (part "EP4CGX30CF23C7N"))
    )
    (comp (ref "R71")
      (value "2k, 1%")
      (footprint "RES0402")
      (fields
        (field (name "MANUFACTURER") "Yageo")
        (field (name "TOLERANCE") "±1%")
        (field (name "MANUFACTURER PART NUMBER") "RC0402FR-072KL")
      )
      (libsource (lib "LimeMicroAltiumLib_schLib") (part "Res_0402"))
    )
  )
  (nets
    (net (code "1") (name "GND") (class "Default")
      (node (ref "C120") (pin "1") (pinfunction "1_1") (pintype "passive"))
      (node (ref "C121") (pin "1") (pinfunction "1_1") (pintype "passive"))
      (node (ref "C122") (pin "1") (pinfunction "1_1") (pintype "passive"))
      (node (ref "C123") (pin "1") (pinfunction "1_1") (pintype "passive"))
      (node (ref "C124") (pin "1") (pinfunction "1_1") (pintype "passive"))
      (node (ref "C125") (pin "2") (pinfunction "2_2") (pintype "passive"))
      (node (ref "C126") (pin "2") (pinfunction "2_2") (pintype "passive"))
      (node (ref "C127") (pin "1") (pinfunction "1_1") (pintype "passive"))
      (node (ref "C128") (pin "1") (pinfunction "1_1") (pintype "passive"))
      (node (ref "C129") (pin "1") (pinfunction "1_1") (pintype "passive"))
      (node (ref "C130") (pin "1") (pinfunction "1_1") (pintype "passive"))
      (node (ref "C131") (pin "2") (pinfunction "2_2") (pintype "passive"))
      (node (ref "C132") (pin "2") (pinfunction "2_2") (pintype "passive"))
      (node (ref "C133") (pin "1") (pinfunction "1_1") (pintype "passive"))
      (node (ref "C134") (pin "1") (pinfunction "1_1") (pintype "passive"))
      (node (ref "C135") (pin "1") (pinfunction "1_1") (pintype "passive"))
      (node (ref "C136") (pin "1") (pinfunction "1_1") (pintype "passive"))
      (node (ref "C137") (pin "1") (pinfunction "1_1") (pintype "passive"))
      (node (ref "C138") (pin "2") (pinfunction "2_2") (pintype "passive"))
      (node (ref "C139") (pin "1") (pinfunction "1_1") (pintype "passive"))
      (node (ref "C140") (pin "1") (pinfunction "1_1") (pintype "passive"))
      (node (ref "C141") (pin "1") (pinfunction "1_1") (pintype "passive"))
      (node (ref "C142") (pin "1") (pinfunction "1_1") (pintype "passive"))
      (node (ref "C143") (pin "1") (pinfunction "1_1") (pintype "passive"))
      (node (ref "C144") (pin "2") (pinfunction "2_2") (pintype "passive"))
      (node (ref "C145") (pin "1") (pinfunction "1_1") (pintype "passive"))
      (node (ref "C146") (pin "1") (pinfunction "1_1") (pintype "passive"))
      (node (ref "C147") (pin "1") (pinfunction "1_1") (pintype "passive"))
      (node (ref "C148") (pin "1") (pinfunction "1_1") (pintype "passive"))
      (node (ref "C149") (pin "1") (pinfunction "1_1") (pintype "passive"))
      (node (ref "C150") (pin "2") (pinfunction "2_2") (pintype "passive"))
      (node (ref "C151") (pin "1") (pinfunction "1_1") (pintype "passive"))
      (node (ref "C152") (pin "1") (pinfunction "1_1") (pintype "passive"))
      (node (ref "C153") (pin "1") (pinfunction "1_1") (pintype "passive"))
      (node (ref "C154") (pin "1") (pinfunction "1_1") (pintype "passive"))
      (node (ref "C155") (pin "1") (pinfunction "1_1") (pintype "passive"))
      (node (ref "C156") (pin "2") (pinfunction "2_2") (pintype "passive"))
      (node (ref "C157") (pin "1") (pinfunction "1_1") (pintype "passive"))
      (node (ref "C158") (pin "1") (pinfunction "1_1") (pintype "passive"))
      (node (ref "C159") (pin "1") (pinfunction "1_1") (pintype "passive"))
      (node (ref "C160") (pin "1") (pinfunction "1_1") (pintype "passive"))
      (node (ref "C161") (pin "1") (pinfunction "1_1") (pintype "passive"))
      (node (ref "C162") (pin "2") (pinfunction "2_2") (pintype "passive"))
      (node (ref "C163") (pin "1") (pinfunction "1_1") (pintype "passive"))
      (node (ref "C164") (pin "1") (pinfunction "1_1") (pintype "passive"))
      (node (ref "C165") (pin "1") (pinfunction "1_1") (pintype "passive"))
      (node (ref "C166") (pin "1") (pinfunction "1_1") (pintype "passive"))
      (node (ref "C167") (pin "1") (pinfunction "1_1") (pintype "passive"))
      (node (ref "C168") (pin "2") (pinfunction "2_2") (pintype "passive"))
      (node (ref "C169") (pin "2") (pinfunction "2_2") (pintype "passive"))
      (node (ref "C170") (pin "2") (pinfunction "2_2") (pintype "passive"))
      (node (ref "C171") (pin "2") (pinfunction "2_2") (pintype "passive"))
      (node (ref "C172") (pin "2") (pinfunction "2_2") (pintype "passive"))
      (node (ref "C173") (pin "2") (pinfunction "2_2") (pintype "passive"))
      (node (ref "C174") (pin "2") (pinfunction "2_2") (pintype "passive"))
      (node (ref "C175") (pin "2") (pinfunction "2_2") (pintype "passive"))
      (node (ref "C176") (pin "2") (pinfunction "2_2") (pintype "passive"))
      (node (ref "C177") (pin "2") (pinfunction "2_2") (pintype "passive"))
      (node (ref "C178") (pin "2") (pinfunction "2_2") (pintype "passive"))
      (node (ref "C179") (pin "2") (pinfunction "2_2") (pintype "passive"))
      (node (ref "C180") (pin "2") (pinfunction "2_2") (pintype "passive"))
      (node (ref "C181") (pin "2") (pinfunction "2_2") (pintype "passive"))
      (node (ref "C182") (pin "2") (pinfunction "2_2") (pintype "passive"))
      (node (ref "C183") (pin "2") (pinfunction "2_2") (pintype "passive"))
      (node (ref "C184") (pin "2") (pinfunction "2_2") (pintype "passive"))
      (node (ref "C185") (pin "2") (pinfunction "2_2") (pintype "passive"))
      (node (ref "C186") (pin "2") (pinfunction "2_2") (pintype "passive"))
      (node (ref "C187") (pin "2") (pinfunction "2_2") (pintype "passive"))
      (node (ref "C188") (pin "2") (pinfunction "2_2") (pintype "passive"))
      (node (ref "C189") (pin "2") (pinfunction "2_2") (pintype "passive"))
      (node (ref "C190") (pin "2") (pinfunction "2_2") (pintype "passive"))
      (node (ref "C191") (pin "2") (pinfunction "2_2") (pintype "passive"))
      (node (ref "C192") (pin "2") (pinfunction "2_2") (pintype "passive"))
      (node (ref "C193") (pin "2") (pinfunction "2_2") (pintype "passive"))
      (node (ref "C194") (pin "2") (pinfunction "2_2") (pintype "passive"))
      (node (ref "C195") (pin "2") (pinfunction "2_2") (pintype "passive"))
      (node (ref "C196") (pin "2") (pinfunction "2_2") (pintype "passive"))
      (node (ref "C197") (pin "2") (pinfunction "2_2") (pintype "passive"))
      (node (ref "C198") (pin "2") (pinfunction "2_2") (pintype "passive"))
      (node (ref "C199") (pin "2") (pinfunction "2_2") (pintype "passive"))
      (node (ref "C200") (pin "2") (pinfunction "2_2") (pintype "passive"))
      (node (ref "C201") (pin "2") (pinfunction "2_2") (pintype "passive"))
      (node (ref "C202") (pin "2") (pinfunction "2_2") (pintype "passive"))
      (node (ref "C203") (pin "2") (pinfunction "2_2") (pintype "passive"))
      (node (ref "C204") (pin "2") (pinfunction "2_2") (pintype "passive"))
      (node (ref "C205") (pin "2") (pinfunction "2_2") (pintype "passive"))
      (node (ref "C206") (pin "2") (pinfunction "2_2") (pintype "passive"))
      (node (ref "C207") (pin "2") (pinfunction "2_2") (pintype "passive"))
      (node (ref "C208") (pin "2") (pinfunction "2_2") (pintype "passive"))
      (node (ref "C209") (pin "2") (pinfunction "2_2") (pintype "passive"))
      (node (ref "C210") (pin "2") (pinfunction "2_2") (pintype "passive"))
      (node (ref "C211") (pin "2") (pinfunction "2_2") (pintype "passive"))
      (node (ref "C212") (pin "2") (pinfunction "2_2") (pintype "passive"))
      (node (ref "C213") (pin "2") (pinfunction "2_2") (pintype "passive"))
      (node (ref "C214") (pin "2") (pinfunction "2_2") (pintype "passive"))
      (node (ref "C215") (pin "2") (pinfunction "2_2") (pintype "passive"))
      (node (ref "C216") (pin "2") (pinfunction "2_2") (pintype "passive"))
      (node (ref "C217") (pin "2") (pinfunction "2_2") (pintype "passive"))
      (node (ref "C218") (pin "2") (pinfunction "2_2") (pintype "passive"))
      (node (ref "C219") (pin "2") (pinfunction "2_2") (pintype "passive"))
      (node (ref "C220") (pin "2") (pinfunction "2_2") (pintype "passive"))
      (node (ref "C221") (pin "2") (pinfunction "2_2") (pintype "passive"))
      (node (ref "C222") (pin "2") (pinfunction "2_2") (pintype "passive"))
      (node (ref "C223") (pin "2") (pinfunction "2_2") (pintype "passive"))
      (node (ref "C224") (pin "2") (pinfunction "2_2") (pintype "passive"))
      (node (ref "C225") (pin "2") (pinfunction "2_2") (pintype "passive"))
      (node (ref "C226") (pin "2") (pinfunction "2_2") (pintype "passive"))
      (node (ref "C227") (pin "2") (pinfunction "2_2") (pintype "passive"))
      (node (ref "C228") (pin "2") (pinfunction "2_2") (pintype "passive"))
      (node (ref "C229") (pin "2") (pinfunction "2_2") (pintype "passive"))
      (node (ref "C230") (pin "2") (pinfunction "2_2") (pintype "passive"))
      (node (ref "C231") (pin "2") (pinfunction "2_2") (pintype "passive"))
      (node (ref "C232") (pin "2") (pinfunction "2_2") (pintype "passive"))
      (node (ref "C233") (pin "2") (pinfunction "2_2") (pintype "passive"))
      (node (ref "C234") (pin "2") (pinfunction "2_2") (pintype "passive"))
      (node (ref "C235") (pin "2") (pinfunction "2_2") (pintype "passive"))
      (node (ref "C236") (pin "2") (pinfunction "2_2") (pintype "passive"))
      (node (ref "C237") (pin "2") (pinfunction "2_2") (pintype "passive"))
      (node (ref "C238") (pin "2") (pinfunction "2_2") (pintype "passive"))
      (node (ref "C239") (pin "2") (pinfunction "2_2") (pintype "passive"))
      (node (ref "C240") (pin "2") (pinfunction "2_2") (pintype "passive"))
      (node (ref "C241") (pin "2") (pinfunction "2_2") (pintype "passive"))
      (node (ref "C242") (pin "2") (pinfunction "2_2") (pintype "passive"))
      (node (ref "C243") (pin "2") (pinfunction "2_2") (pintype "passive"))
      (node (ref "C244") (pin "2") (pinfunction "2_2") (pintype "passive"))
      (node (ref "C245") (pin "2") (pinfunction "2_2") (pintype "passive"))
      (node (ref "C246") (pin "2") (pinfunction "2_2") (pintype "passive"))
      (node (ref "C247") (pin "2") (pinfunction "2_2") (pintype "passive"))
      (node (ref "C248") (pin "2") (pinfunction "2_2") (pintype "passive"))
      (node (ref "C249") (pin "2") (pinfunction "2_2") (pintype "passive"))
      (node (ref "C250") (pin "2") (pinfunction "2_2") (pintype "passive"))
      (node (ref "IC8") (pin "AA1") (pinfunction "GND_AA1") (pintype "passive"))
      (node (ref "IC8") (pin "AA11") (pinfunction "GND_AA11") (pintype "passive"))
      (node (ref "IC8") (pin "AA14") (pinfunction "GND_AA14") (pintype "passive"))
      (node (ref "IC8") (pin "AA17") (pinfunction "GND_AA17") (pintype "passive"))
      (node (ref "IC8") (pin "AA2") (pinfunction "GND_AA2") (pintype "passive"))
      (node (ref "IC8") (pin "AA5") (pinfunction "GND_AA5") (pintype "passive"))
      (node (ref "IC8") (pin "AA8") (pinfunction "GND_AA8") (pintype "passive"))
      (node (ref "IC8") (pin "AB2") (pinfunction "GND_AB2") (pintype "passive"))
      (node (ref "IC8") (pin "B11") (pinfunction "GND_B11") (pintype "passive"))
      (node (ref "IC8") (pin "B14") (pinfunction "GND_B14") (pintype "passive"))
      (node (ref "IC8") (pin "B17") (pinfunction "GND_B17") (pintype "passive"))
      (node (ref "IC8") (pin "B2") (pinfunction "GND_B2") (pintype "passive"))
      (node (ref "IC8") (pin "B5") (pinfunction "GND_B5") (pintype "passive"))
      (node (ref "IC8") (pin "B8") (pinfunction "GND_B8") (pintype "passive"))
      (node (ref "IC8") (pin "C21") (pinfunction "GND_C21") (pintype "passive"))
      (node (ref "IC8") (pin "D18") (pinfunction "GND_D18") (pintype "passive"))
      (node (ref "IC8") (pin "E1") (pinfunction "GND_E1") (pintype "passive"))
      (node (ref "IC8") (pin "E19") (pinfunction "GND_E19") (pintype "passive"))
      (node (ref "IC8") (pin "E2") (pinfunction "GND_E2") (pintype "passive"))
      (node (ref "IC8") (pin "E7") (pinfunction "GND_E7") (pintype "passive"))
      (node (ref "IC8") (pin "F11") (pinfunction "GND_F11") (pintype "passive"))
      (node (ref "IC8") (pin "F13") (pinfunction "GND_F13") (pintype "passive"))
      (node (ref "IC8") (pin "F15") (pinfunction "GND_F15") (pintype "passive"))
      (node (ref "IC8") (pin "F21") (pinfunction "GND_F21") (pintype "passive"))
      (node (ref "IC8") (pin "F3") (pinfunction "GND_F3") (pintype "passive"))
      (node (ref "IC8") (pin "F9") (pinfunction "GND_F9") (pintype "passive"))
      (node (ref "IC8") (pin "G1") (pinfunction "GND_G1") (pintype "passive"))
      (node (ref "IC8") (pin "G2") (pinfunction "GND_G2") (pintype "passive"))
      (node (ref "IC8") (pin "H11") (pinfunction "GND_H11") (pintype "passive"))
      (node (ref "IC8") (pin "H18") (pinfunction "GND_H18") (pintype "passive"))
      (node (ref "IC8") (pin "H5") (pinfunction "GND_H5") (pintype "passive"))
      (node (ref "IC8") (pin "J1") (pinfunction "GND_J1") (pintype "passive"))
      (node (ref "IC8") (pin "J2") (pinfunction "GND_J2") (pintype "passive"))
      (node (ref "IC8") (pin "J6") (pinfunction "GND_J6") (pintype "passive"))
      (node (ref "IC8") (pin "J8") (pinfunction "GND_J8") (pintype "passive"))
      (node (ref "IC8") (pin "K11") (pinfunction "GND_K11") (pintype "passive"))
      (node (ref "IC8") (pin "K15") (pinfunction "GND_K15") (pintype "passive"))
      (node (ref "IC8") (pin "K21") (pinfunction "GND_K21") (pintype "passive"))
      (node (ref "IC8") (pin "K5") (pinfunction "GND_K5") (pintype "passive"))
      (node (ref "IC8") (pin "K7") (pinfunction "GND_K7") (pintype "passive"))
      (node (ref "IC8") (pin "K9") (pinfunction "GND_K9") (pintype "passive"))
      (node (ref "IC8") (pin "L1") (pinfunction "GND_L1") (pintype "passive"))
      (node (ref "IC8") (pin "L10") (pinfunction "GND_L10") (pintype "passive"))
      (node (ref "IC8") (pin "L12") (pinfunction "GND_L12") (pintype "passive"))
      (node (ref "IC8") (pin "L18") (pinfunction "GND_L18") (pintype "passive"))
      (node (ref "IC8") (pin "L2") (pinfunction "GND_L2") (pintype "passive"))
      (node (ref "IC8") (pin "L6") (pinfunction "GND_L6") (pintype "passive"))
      (node (ref "IC8") (pin "L8") (pinfunction "GND_L8") (pintype "passive"))
      (node (ref "IC8") (pin "M3") (pinfunction "GND_M3") (pintype "passive"))
      (node (ref "IC8") (pin "M5") (pinfunction "GND_M5") (pintype "passive"))
      (node (ref "IC8") (pin "M9") (pinfunction "GND_M9") (pintype "passive"))
      (node (ref "IC8") (pin "N1") (pinfunction "GND_N1") (pintype "passive"))
      (node (ref "IC8") (pin "N10") (pinfunction "GND_N10") (pintype "passive"))
      (node (ref "IC8") (pin "N2") (pinfunction "GND_N2") (pintype "passive"))
      (node (ref "IC8") (pin "N4") (pinfunction "GND_N4") (pintype "passive"))
      (node (ref "IC8") (pin "N6") (pinfunction "GND_N6") (pintype "passive"))
      (node (ref "IC8") (pin "P11") (pinfunction "GND_P11") (pintype "passive"))
      (node (ref "IC8") (pin "P16") (pinfunction "GND_P16") (pintype "passive"))
      (node (ref "IC8") (pin "P18") (pinfunction "GND_P18") (pintype "passive"))
      (node (ref "IC8") (pin "P21") (pinfunction "GND_P21") (pintype "passive"))
      (node (ref "IC8") (pin "P9") (pinfunction "GND_P9") (pintype "passive"))
      (node (ref "IC8") (pin "R1") (pinfunction "GND_R1") (pintype "passive"))
      (node (ref "IC8") (pin "R12") (pinfunction "GND_R12") (pintype "passive"))
      (node (ref "IC8") (pin "R2") (pinfunction "GND_R2") (pintype "passive"))
      (node (ref "IC8") (pin "R6") (pinfunction "GND_R6") (pintype "passive"))
      (node (ref "IC8") (pin "T4") (pinfunction "GND_T4") (pintype "passive"))
      (node (ref "IC8") (pin "U1") (pinfunction "GND_U1") (pintype "passive"))
      (node (ref "IC8") (pin "U10") (pinfunction "GND_U10") (pintype "passive"))
      (node (ref "IC8") (pin "U17") (pinfunction "GND_U17") (pintype "passive"))
      (node (ref "IC8") (pin "U2") (pinfunction "GND_U2") (pintype "passive"))
      (node (ref "IC8") (pin "U21") (pinfunction "GND_U21") (pintype "passive"))
      (node (ref "IC8") (pin "U3") (pinfunction "GND_U3") (pintype "passive"))
      (node (ref "IC8") (pin "V11") (pinfunction "GND_V11") (pintype "passive"))
      (node (ref "IC8") (pin "V14") (pinfunction "GND_V14") (pintype "passive"))
      (node (ref "IC8") (pin "V19") (pinfunction "GND_V19") (pintype "passive"))
      (node (ref "IC8") (pin "V5") (pinfunction "GND_V5") (pintype "passive"))
      (node (ref "IC8") (pin "V8") (pinfunction "GND_V8") (pintype "passive"))
      (node (ref "IC8") (pin "W1") (pinfunction "GND_W1") (pintype "passive"))
      (node (ref "IC8") (pin "W2") (pinfunction "GND_W2") (pintype "passive"))
      (node (ref "IC8") (pin "Y21") (pinfunction "GND_Y21") (pintype "passive"))
      (node (ref "R71") (pin "2") (pinfunction "2_2") (pintype "passive"))
    )
    (net (code "2") (name "Net-(IC8J-RREF0)") (class "Default")
      (node (ref "IC8") (pin "AB1") (pinfunction "RREF0_AB1") (pintype "bidirectional"))
      (node (ref "R71") (pin "1") (pinfunction "1_1") (pintype "passive"))
    )
    (net (code "3") (name "VCC1P2") (class "Default")
      (node (ref "C120") (pin "2") (pinfunction "2_2") (pintype "passive"))
      (node (ref "C121") (pin "2") (pinfunction "2_2") (pintype "passive"))
      (node (ref "C122") (pin "2") (pinfunction "2_2") (pintype "passive"))
      (node (ref "C123") (pin "2") (pinfunction "2_2") (pintype "passive"))
      (node (ref "C124") (pin "2") (pinfunction "2_2") (pintype "passive"))
      (node (ref "C125") (pin "1") (pinfunction "1_1") (pintype "passive"))
      (node (ref "C126") (pin "1") (pinfunction "1_1") (pintype "passive"))
      (node (ref "C213") (pin "1") (pinfunction "1_1") (pintype "passive"))
      (node (ref "C214") (pin "1") (pinfunction "1_1") (pintype "passive"))
      (node (ref "C215") (pin "1") (pinfunction "1_1") (pintype "passive"))
      (node (ref "C216") (pin "1") (pinfunction "1_1") (pintype "passive"))
      (node (ref "C217") (pin "1") (pinfunction "1_1") (pintype "passive"))
      (node (ref "C218") (pin "1") (pinfunction "1_1") (pintype "passive"))
      (node (ref "C219") (pin "1") (pinfunction "1_1") (pintype "passive"))
      (node (ref "C220") (pin "1") (pinfunction "1_1") (pintype "passive"))
      (node (ref "C221") (pin "1") (pinfunction "1_1") (pintype "passive"))
      (node (ref "C222") (pin "1") (pinfunction "1_1") (pintype "passive"))
      (node (ref "C223") (pin "1") (pinfunction "1_1") (pintype "passive"))
      (node (ref "C224") (pin "1") (pinfunction "1_1") (pintype "passive"))
      (node (ref "C225") (pin "1") (pinfunction "1_1") (pintype "passive"))
      (node (ref "C226") (pin "1") (pinfunction "1_1") (pintype "passive"))
      (node (ref "C227") (pin "1") (pinfunction "1_1") (pintype "passive"))
      (node (ref "C235") (pin "1") (pinfunction "1_1") (pintype "passive"))
      (node (ref "C236") (pin "1") (pinfunction "1_1") (pintype "passive"))
      (node (ref "C237") (pin "1") (pinfunction "1_1") (pintype "passive"))
      (node (ref "C238") (pin "1") (pinfunction "1_1") (pintype "passive"))
      (node (ref "C239") (pin "1") (pinfunction "1_1") (pintype "passive"))
      (node (ref "C240") (pin "1") (pinfunction "1_1") (pintype "passive"))
      (node (ref "C241") (pin "1") (pinfunction "1_1") (pintype "passive"))
      (node (ref "C242") (pin "1") (pinfunction "1_1") (pintype "passive"))
      (node (ref "C243") (pin "1") (pinfunction "1_1") (pintype "passive"))
      (node (ref "C244") (pin "1") (pinfunction "1_1") (pintype "passive"))
      (node (ref "C245") (pin "1") (pinfunction "1_1") (pintype "passive"))
      (node (ref "C246") (pin "1") (pinfunction "1_1") (pintype "passive"))
      (node (ref "C247") (pin "1") (pinfunction "1_1") (pintype "passive"))
      (node (ref "C248") (pin "1") (pinfunction "1_1") (pintype "passive"))
      (node (ref "C249") (pin "1") (pinfunction "1_1") (pintype "passive"))
      (node (ref "C250") (pin "1") (pinfunction "1_1") (pintype "passive"))
      (node (ref "FR36") (pin "1") (pinfunction "1_1") (pintype "passive"))
      (node (ref "FR37") (pin "1") (pinfunction "1_1") (pintype "passive"))
      (node (ref "IC8") (pin "F7") (pinfunction "VCCINT_F7") (pintype "bidirectional"))
      (node (ref "IC8") (pin "G13") (pinfunction "VCCINT_G13") (pintype "bidirectional"))
      (node (ref "IC8") (pin "G9") (pinfunction "VCCINT_G9") (pintype "bidirectional"))
      (node (ref "IC8") (pin "H6") (pinfunction "VCCINT_H6") (pintype "bidirectional"))
      (node (ref "IC8") (pin "J11") (pinfunction "VCCINT_J11") (pintype "bidirectional"))
      (node (ref "IC8") (pin "J17") (pinfunction "VCCINT_J17") (pintype "bidirectional"))
      (node (ref "IC8") (pin "J5") (pinfunction "VCCINT_J5") (pintype "bidirectional"))
      (node (ref "IC8") (pin "J7") (pinfunction "VCCINT_J7") (pintype "bidirectional"))
      (node (ref "IC8") (pin "J9") (pinfunction "VCCINT_J9") (pintype "bidirectional"))
      (node (ref "IC8") (pin "K16") (pinfunction "VCCINT_K16") (pintype "bidirectional"))
      (node (ref "IC8") (pin "K6") (pinfunction "VCCINT_K6") (pintype "bidirectional"))
      (node (ref "IC8") (pin "K8") (pinfunction "VCCINT_K8") (pintype "bidirectional"))
      (node (ref "IC8") (pin "L11") (pinfunction "VCCINT_L11") (pintype "bidirectional"))
      (node (ref "IC8") (pin "L17") (pinfunction "VCCINT_L17") (pintype "bidirectional"))
      (node (ref "IC8") (pin "L5") (pinfunction "VCCINT_L5") (pintype "bidirectional"))
      (node (ref "IC8") (pin "L7") (pinfunction "VCCINT_L7") (pintype "bidirectional"))
      (node (ref "IC8") (pin "L9") (pinfunction "VCCINT_L9") (pintype "bidirectional"))
      (node (ref "IC8") (pin "M10") (pinfunction "VCCINT_M10") (pintype "bidirectional"))
      (node (ref "IC8") (pin "M12") (pinfunction "VCCINT_M12") (pintype "bidirectional"))
      (node (ref "IC8") (pin "M6") (pinfunction "VCCINT_M6") (pintype "bidirectional"))
      (node (ref "IC8") (pin "N16") (pinfunction "VCCINT_N16") (pintype "bidirectional"))
      (node (ref "IC8") (pin "N5") (pinfunction "VCCINT_N5") (pintype "bidirectional"))
      (node (ref "IC8") (pin "N9") (pinfunction "VCCINT_N9") (pintype "bidirectional"))
      (node (ref "IC8") (pin "P12") (pinfunction "VCCINT_P12") (pintype "bidirectional"))
      (node (ref "IC8") (pin "P17") (pinfunction "VCCINT_P17") (pintype "bidirectional"))
      (node (ref "IC8") (pin "P6") (pinfunction "VCCINT_P6") (pintype "bidirectional"))
      (node (ref "IC8") (pin "P8") (pinfunction "VCCINT_P8") (pintype "bidirectional"))
      (node (ref "IC8") (pin "R7") (pinfunction "VCCINT_R7") (pintype "bidirectional"))
      (node (ref "IC8") (pin "T10") (pinfunction "VCCINT_T10") (pintype "bidirectional"))
      (node (ref "IC8") (pin "T12") (pinfunction "VCCINT_T12") (pintype "bidirectional"))
      (node (ref "IC8") (pin "U16") (pinfunction "VCCINT_U16") (pintype "bidirectional"))
    )
    (net (code "4") (name "VCC1P2D_FPGA") (class "Default")
      (node (ref "C127") (pin "2") (pinfunction "2_2") (pintype "passive"))
      (node (ref "C128") (pin "2") (pinfunction "2_2") (pintype "passive"))
      (node (ref "C129") (pin "2") (pinfunction "2_2") (pintype "passive"))
      (node (ref "C130") (pin "2") (pinfunction "2_2") (pintype "passive"))
      (node (ref "C131") (pin "1") (pinfunction "1_1") (pintype "passive"))
      (node (ref "C132") (pin "1") (pinfunction "1_1") (pintype "passive"))
      (node (ref "C207") (pin "1") (pinfunction "1_1") (pintype "passive"))
      (node (ref "C208") (pin "1") (pinfunction "1_1") (pintype "passive"))
      (node (ref "C209") (pin "1") (pinfunction "1_1") (pintype "passive"))
      (node (ref "C210") (pin "1") (pinfunction "1_1") (pintype "passive"))
      (node (ref "C211") (pin "1") (pinfunction "1_1") (pintype "passive"))
      (node (ref "C212") (pin "1") (pinfunction "1_1") (pintype "passive"))
      (node (ref "FR36") (pin "2") (pinfunction "2_2") (pintype "passive"))
      (node (ref "IC8") (pin "E18") (pinfunction "VCCD_PLL_E18") (pintype "bidirectional"))
      (node (ref "IC8") (pin "G3") (pinfunction "VCCD_PLL_G3") (pintype "bidirectional"))
      (node (ref "IC8") (pin "M4") (pinfunction "VCCD_PLL_M4") (pintype "bidirectional"))
      (node (ref "IC8") (pin "R4") (pinfunction "VCCD_PLL_R4") (pintype "bidirectional"))
      (node (ref "IC8") (pin "U4") (pinfunction "VCCD_PLL_U4") (pintype "bidirectional"))
      (node (ref "IC8") (pin "V18") (pinfunction "VCCD_PLL_V18") (pintype "bidirectional"))
    )
    (net (code "5") (name "VCC1P2L_FPGA") (class "Default")
      (node (ref "C133") (pin "2") (pinfunction "2_2") (pintype "passive"))
      (node (ref "C134") (pin "2") (pinfunction "2_2") (pintype "passive"))
      (node (ref "C135") (pin "2") (pinfunction "2_2") (pintype "passive"))
      (node (ref "C136") (pin "2") (pinfunction "2_2") (pintype "passive"))
      (node (ref "C137") (pin "2") (pinfunction "2_2") (pintype "passive"))
      (node (ref "C138") (pin "1") (pinfunction "1_1") (pintype "passive"))
      (node (ref "C169") (pin "1") (pinfunction "1_1") (pintype "passive"))
      (node (ref "C170") (pin "1") (pinfunction "1_1") (pintype "passive"))
      (node (ref "C171") (pin "1") (pinfunction "1_1") (pintype "passive"))
      (node (ref "C172") (pin "1") (pinfunction "1_1") (pintype "passive"))
      (node (ref "C173") (pin "1") (pinfunction "1_1") (pintype "passive"))
      (node (ref "FR37") (pin "2") (pinfunction "2_2") (pintype "passive"))
      (node (ref "IC8") (pin "K3") (pinfunction "VCCL_GXB_K3") (pintype "bidirectional"))
      (node (ref "IC8") (pin "L3") (pinfunction "VCCL_GXB_L3") (pintype "bidirectional"))
      (node (ref "IC8") (pin "N3") (pinfunction "VCCL_GXB_N3") (pintype "bidirectional"))
      (node (ref "IC8") (pin "T3") (pinfunction "VCCL_GXB_T3") (pintype "bidirectional"))
      (node (ref "IC8") (pin "V3") (pinfunction "VCCL_GXB_V3") (pintype "bidirectional"))
    )
    (net (code "6") (name "VCC1P8") (class "Default")
      (node (ref "C139") (pin "2") (pinfunction "2_2") (pintype "passive"))
      (node (ref "C140") (pin "2") (pinfunction "2_2") (pintype "passive"))
      (node (ref "C141") (pin "2") (pinfunction "2_2") (pintype "passive"))
      (node (ref "C142") (pin "2") (pinfunction "2_2") (pintype "passive"))
      (node (ref "C143") (pin "2") (pinfunction "2_2") (pintype "passive"))
      (node (ref "C144") (pin "1") (pinfunction "1_1") (pintype "passive"))
      (node (ref "C195") (pin "1") (pinfunction "1_1") (pintype "passive"))
      (node (ref "C196") (pin "1") (pinfunction "1_1") (pintype "passive"))
      (node (ref "C197") (pin "1") (pinfunction "1_1") (pintype "passive"))
      (node (ref "C198") (pin "1") (pinfunction "1_1") (pintype "passive"))
      (node (ref "C199") (pin "1") (pinfunction "1_1") (pintype "passive"))
      (node (ref "C200") (pin "1") (pinfunction "1_1") (pintype "passive"))
      (node (ref "C201") (pin "1") (pinfunction "1_1") (pintype "passive"))
      (node (ref "C202") (pin "1") (pinfunction "1_1") (pintype "passive"))
      (node (ref "C203") (pin "1") (pinfunction "1_1") (pintype "passive"))
      (node (ref "C204") (pin "1") (pinfunction "1_1") (pintype "passive"))
      (node (ref "C205") (pin "1") (pinfunction "1_1") (pintype "passive"))
      (node (ref "C206") (pin "1") (pinfunction "1_1") (pintype "passive"))
      (node (ref "IC8") (pin "N18") (pinfunction "VCCIO5_N18") (pintype "bidirectional"))
      (node (ref "IC8") (pin "P19") (pinfunction "VCCIO5_P19") (pintype "bidirectional"))
      (node (ref "IC8") (pin "R18") (pinfunction "VCCIO5_R18") (pintype "bidirectional"))
      (node (ref "IC8") (pin "U11") (pinfunction "VCCIO3_U11") (pintype "bidirectional"))
      (node (ref "IC8") (pin "U13") (pinfunction "VCCIO4_U13") (pintype "bidirectional"))
      (node (ref "IC8") (pin "U8") (pinfunction "VCCIO3_U8") (pintype "bidirectional"))
      (node (ref "IC8") (pin "U9") (pinfunction "VCCIO3_U9") (pintype "bidirectional"))
      (node (ref "IC8") (pin "V10") (pinfunction "VCCIO3_V10") (pintype "bidirectional"))
      (node (ref "IC8") (pin "V12") (pinfunction "VCCIO3_V12") (pintype "bidirectional"))
      (node (ref "IC8") (pin "V15") (pinfunction "VCCIO4_V15") (pintype "bidirectional"))
      (node (ref "IC8") (pin "V16") (pinfunction "VCCIO4_V16") (pintype "bidirectional"))
      (node (ref "IC8") (pin "V17") (pinfunction "VCCIO4_V17") (pintype "bidirectional"))
    )
    (net (code "7") (name "VCC2P5") (class "Default")
      (node (ref "FR38") (pin "1") (pinfunction "1_1") (pintype "passive"))
      (node (ref "FR39") (pin "1") (pinfunction "1_1") (pintype "passive"))
    )
    (net (code "8") (name "VCC2P5AH_FPGA") (class "Default")
      (node (ref "C151") (pin "2") (pinfunction "2_2") (pintype "passive"))
      (node (ref "C152") (pin "2") (pinfunction "2_2") (pintype "passive"))
      (node (ref "C153") (pin "2") (pinfunction "2_2") (pintype "passive"))
      (node (ref "C154") (pin "2") (pinfunction "2_2") (pintype "passive"))
      (node (ref "C155") (pin "2") (pinfunction "2_2") (pintype "passive"))
      (node (ref "C156") (pin "1") (pinfunction "1_1") (pintype "passive"))
      (node (ref "C183") (pin "1") (pinfunction "1_1") (pintype "passive"))
      (node (ref "C184") (pin "1") (pinfunction "1_1") (pintype "passive"))
      (node (ref "C185") (pin "1") (pinfunction "1_1") (pintype "passive"))
      (node (ref "C186") (pin "1") (pinfunction "1_1") (pintype "passive"))
      (node (ref "C187") (pin "1") (pinfunction "1_1") (pintype "passive"))
      (node (ref "FR39") (pin "2") (pinfunction "2_2") (pintype "passive"))
      (node (ref "IC8") (pin "H3") (pinfunction "VCCH_GXB_H3") (pintype "bidirectional"))
      (node (ref "IC8") (pin "J3") (pinfunction "VCCA_GXB_J3") (pintype "bidirectional"))
      (node (ref "IC8") (pin "P3") (pinfunction "VCCH_GXB_P3") (pintype "bidirectional"))
      (node (ref "IC8") (pin "R3") (pinfunction "VCCA_GXB_R3") (pintype "bidirectional"))
      (node (ref "IC8") (pin "W3") (pinfunction "VCCA_GXB_W3") (pintype "bidirectional"))
    )
    (net (code "9") (name "VCC2P5A_FPGA") (class "Default")
      (node (ref "C145") (pin "2") (pinfunction "2_2") (pintype "passive"))
      (node (ref "C146") (pin "2") (pinfunction "2_2") (pintype "passive"))
      (node (ref "C147") (pin "2") (pinfunction "2_2") (pintype "passive"))
      (node (ref "C148") (pin "2") (pinfunction "2_2") (pintype "passive"))
      (node (ref "C149") (pin "2") (pinfunction "2_2") (pintype "passive"))
      (node (ref "C150") (pin "1") (pinfunction "1_1") (pintype "passive"))
      (node (ref "C188") (pin "1") (pinfunction "1_1") (pintype "passive"))
      (node (ref "C189") (pin "1") (pinfunction "1_1") (pintype "passive"))
      (node (ref "C190") (pin "1") (pinfunction "1_1") (pintype "passive"))
      (node (ref "C191") (pin "1") (pinfunction "1_1") (pintype "passive"))
      (node (ref "C192") (pin "1") (pinfunction "1_1") (pintype "passive"))
      (node (ref "C193") (pin "1") (pinfunction "1_1") (pintype "passive"))
      (node (ref "C194") (pin "1") (pinfunction "1_1") (pintype "passive"))
      (node (ref "FR38") (pin "2") (pinfunction "2_2") (pintype "passive"))
      (node (ref "IC8") (pin "F19") (pinfunction "VCCA_F19") (pintype "bidirectional"))
      (node (ref "IC8") (pin "F4") (pinfunction "VCCA_F4") (pintype "bidirectional"))
      (node (ref "IC8") (pin "L4") (pinfunction "VCCA_L4") (pintype "bidirectional"))
      (node (ref "IC8") (pin "N12") (pinfunction "VCC_CLKIN3A_N12") (pintype "bidirectional"))
      (node (ref "IC8") (pin "T5") (pinfunction "VCCA_T5") (pintype "bidirectional"))
      (node (ref "IC8") (pin "U19") (pinfunction "VCCA_U19") (pintype "bidirectional"))
      (node (ref "IC8") (pin "V4") (pinfunction "VCCA_V4") (pintype "bidirectional"))
    )
    (net (code "10") (name "VCC3P3") (class "Default")
      (node (ref "C163") (pin "2") (pinfunction "2_2") (pintype "passive"))
      (node (ref "C164") (pin "2") (pinfunction "2_2") (pintype "passive"))
      (node (ref "C165") (pin "2") (pinfunction "2_2") (pintype "passive"))
      (node (ref "C166") (pin "2") (pinfunction "2_2") (pintype "passive"))
      (node (ref "C167") (pin "2") (pinfunction "2_2") (pintype "passive"))
      (node (ref "C168") (pin "1") (pinfunction "1_1") (pintype "passive"))
      (node (ref "C174") (pin "1") (pinfunction "1_1") (pintype "passive"))
      (node (ref "C175") (pin "1") (pinfunction "1_1") (pintype "passive"))
      (node (ref "C176") (pin "1") (pinfunction "1_1") (pintype "passive"))
      (node (ref "C177") (pin "1") (pinfunction "1_1") (pintype "passive"))
      (node (ref "C178") (pin "1") (pinfunction "1_1") (pintype "passive"))
      (node (ref "C179") (pin "1") (pinfunction "1_1") (pintype "passive"))
      (node (ref "C180") (pin "1") (pinfunction "1_1") (pintype "passive"))
      (node (ref "C181") (pin "1") (pinfunction "1_1") (pintype "passive"))
      (node (ref "C182") (pin "1") (pinfunction "1_1") (pintype "passive"))
      (node (ref "IC8") (pin "E13") (pinfunction "VCCIO7_E13") (pintype "bidirectional"))
      (node (ref "IC8") (pin "E14") (pinfunction "VCCIO7_E14") (pintype "bidirectional"))
      (node (ref "IC8") (pin "E15") (pinfunction "VCCIO7_E15") (pintype "bidirectional"))
      (node (ref "IC8") (pin "E16") (pinfunction "VCCIO7_E16") (pintype "bidirectional"))
      (node (ref "IC8") (pin "F14") (pinfunction "VCCIO7_F14") (pintype "bidirectional"))
      (node (ref "IC8") (pin "G4") (pinfunction "VCCIO9_G4") (pintype "bidirectional"))
      (node (ref "IC8") (pin "H19") (pinfunction "VCCIO6_H19") (pintype "bidirectional"))
      (node (ref "IC8") (pin "J18") (pinfunction "VCCIO6_J18") (pintype "bidirectional"))
      (node (ref "IC8") (pin "K18") (pinfunction "VCCIO6_K18") (pintype "bidirectional"))
    )
    (net (code "11") (name "VDIO_LMS_FPGA") (class "Default")
      (node (ref "C157") (pin "2") (pinfunction "2_2") (pintype "passive"))
      (node (ref "C158") (pin "2") (pinfunction "2_2") (pintype "passive"))
      (node (ref "C159") (pin "2") (pinfunction "2_2") (pintype "passive"))
      (node (ref "C160") (pin "2") (pinfunction "2_2") (pintype "passive"))
      (node (ref "C161") (pin "2") (pinfunction "2_2") (pintype "passive"))
      (node (ref "C162") (pin "1") (pinfunction "1_1") (pintype "passive"))
      (node (ref "C228") (pin "1") (pinfunction "1_1") (pintype "passive"))
      (node (ref "C229") (pin "1") (pinfunction "1_1") (pintype "passive"))
      (node (ref "C230") (pin "1") (pinfunction "1_1") (pintype "passive"))
      (node (ref "C231") (pin "1") (pinfunction "1_1") (pintype "passive"))
      (node (ref "C232") (pin "1") (pinfunction "1_1") (pintype "passive"))
      (node (ref "C233") (pin "1") (pinfunction "1_1") (pintype "passive"))
      (node (ref "C234") (pin "1") (pinfunction "1_1") (pintype "passive"))
      (node (ref "IC8") (pin "E10") (pinfunction "VCCIO8_E10") (pintype "bidirectional"))
      (node (ref "IC8") (pin "E11") (pinfunction "VCCIO8_E11") (pintype "bidirectional"))
      (node (ref "IC8") (pin "E12") (pinfunction "VCCIO8_E12") (pintype "bidirectional"))
      (node (ref "IC8") (pin "E9") (pinfunction "VCCIO8_E9") (pintype "bidirectional"))
      (node (ref "IC8") (pin "F10") (pinfunction "VCCIO8_F10") (pintype "bidirectional"))
      (node (ref "IC8") (pin "H10") (pinfunction "VCC_CLKIN8A_H10") (pintype "bidirectional"))
      (node (ref "IC8") (pin "P7") (pinfunction "VCC_CLKIN3B_P7") (pintype "bidirectional"))
    )
    (net (code "12") (name "unconnected-(IC8J-NC-PadAA3)") (class "Default")
      (node (ref "IC8") (pin "AA3") (pinfunction "NC_AA3") (pintype "bidirectional+no_connect"))
    )
    (net (code "13") (name "unconnected-(IC8J-NC-PadY3)") (class "Default")
      (node (ref "IC8") (pin "Y3") (pinfunction "NC_Y3") (pintype "bidirectional+no_connect"))
    )
  )
)
